# lapwing2p2.net
KiCad netlist of a schematic drawn in Altium Designer
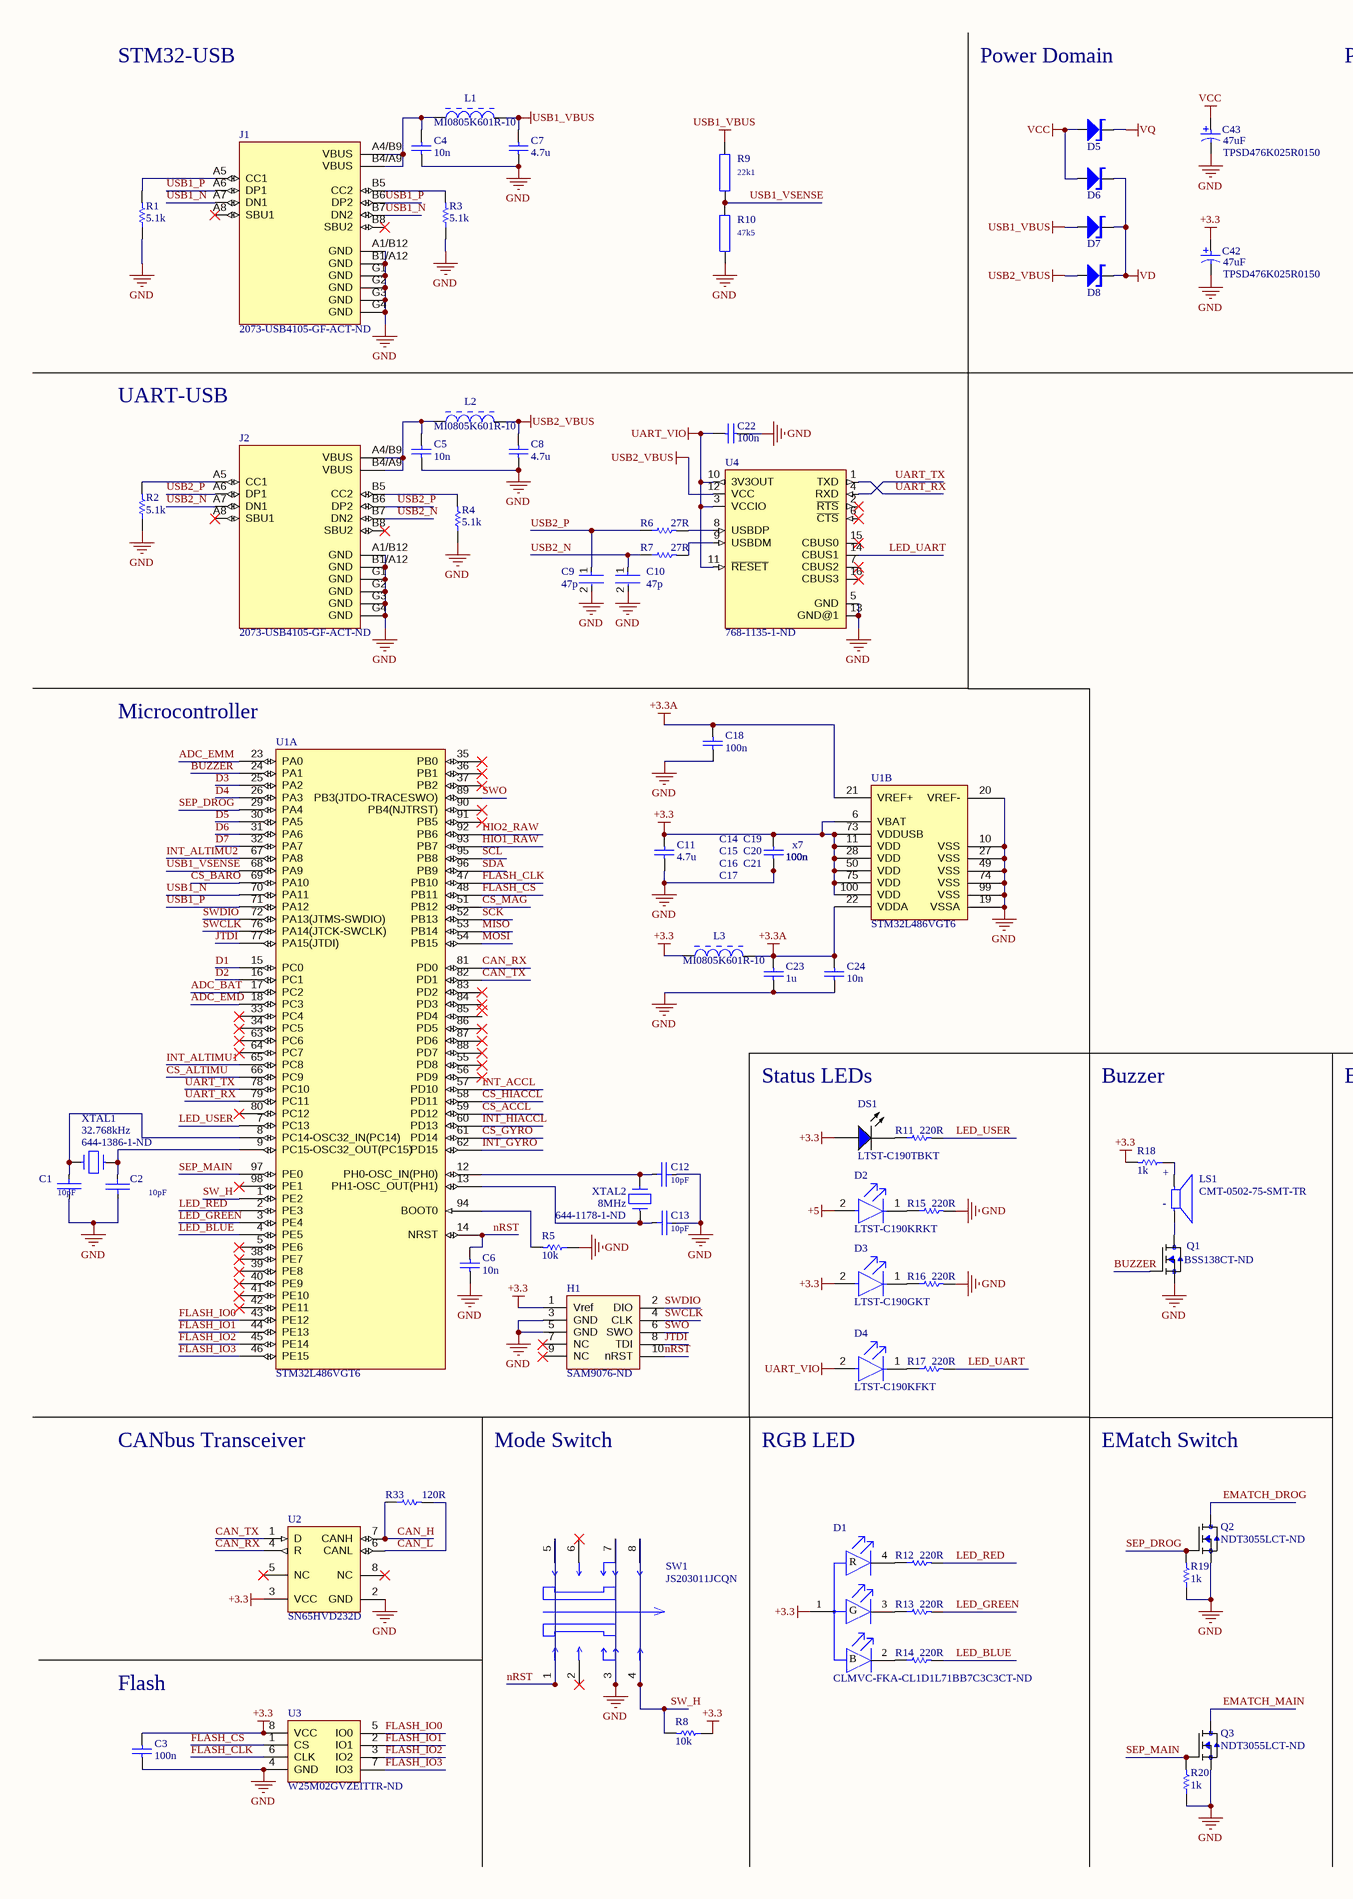
[diagram p0: lapwing2p2.SchDoc, left]
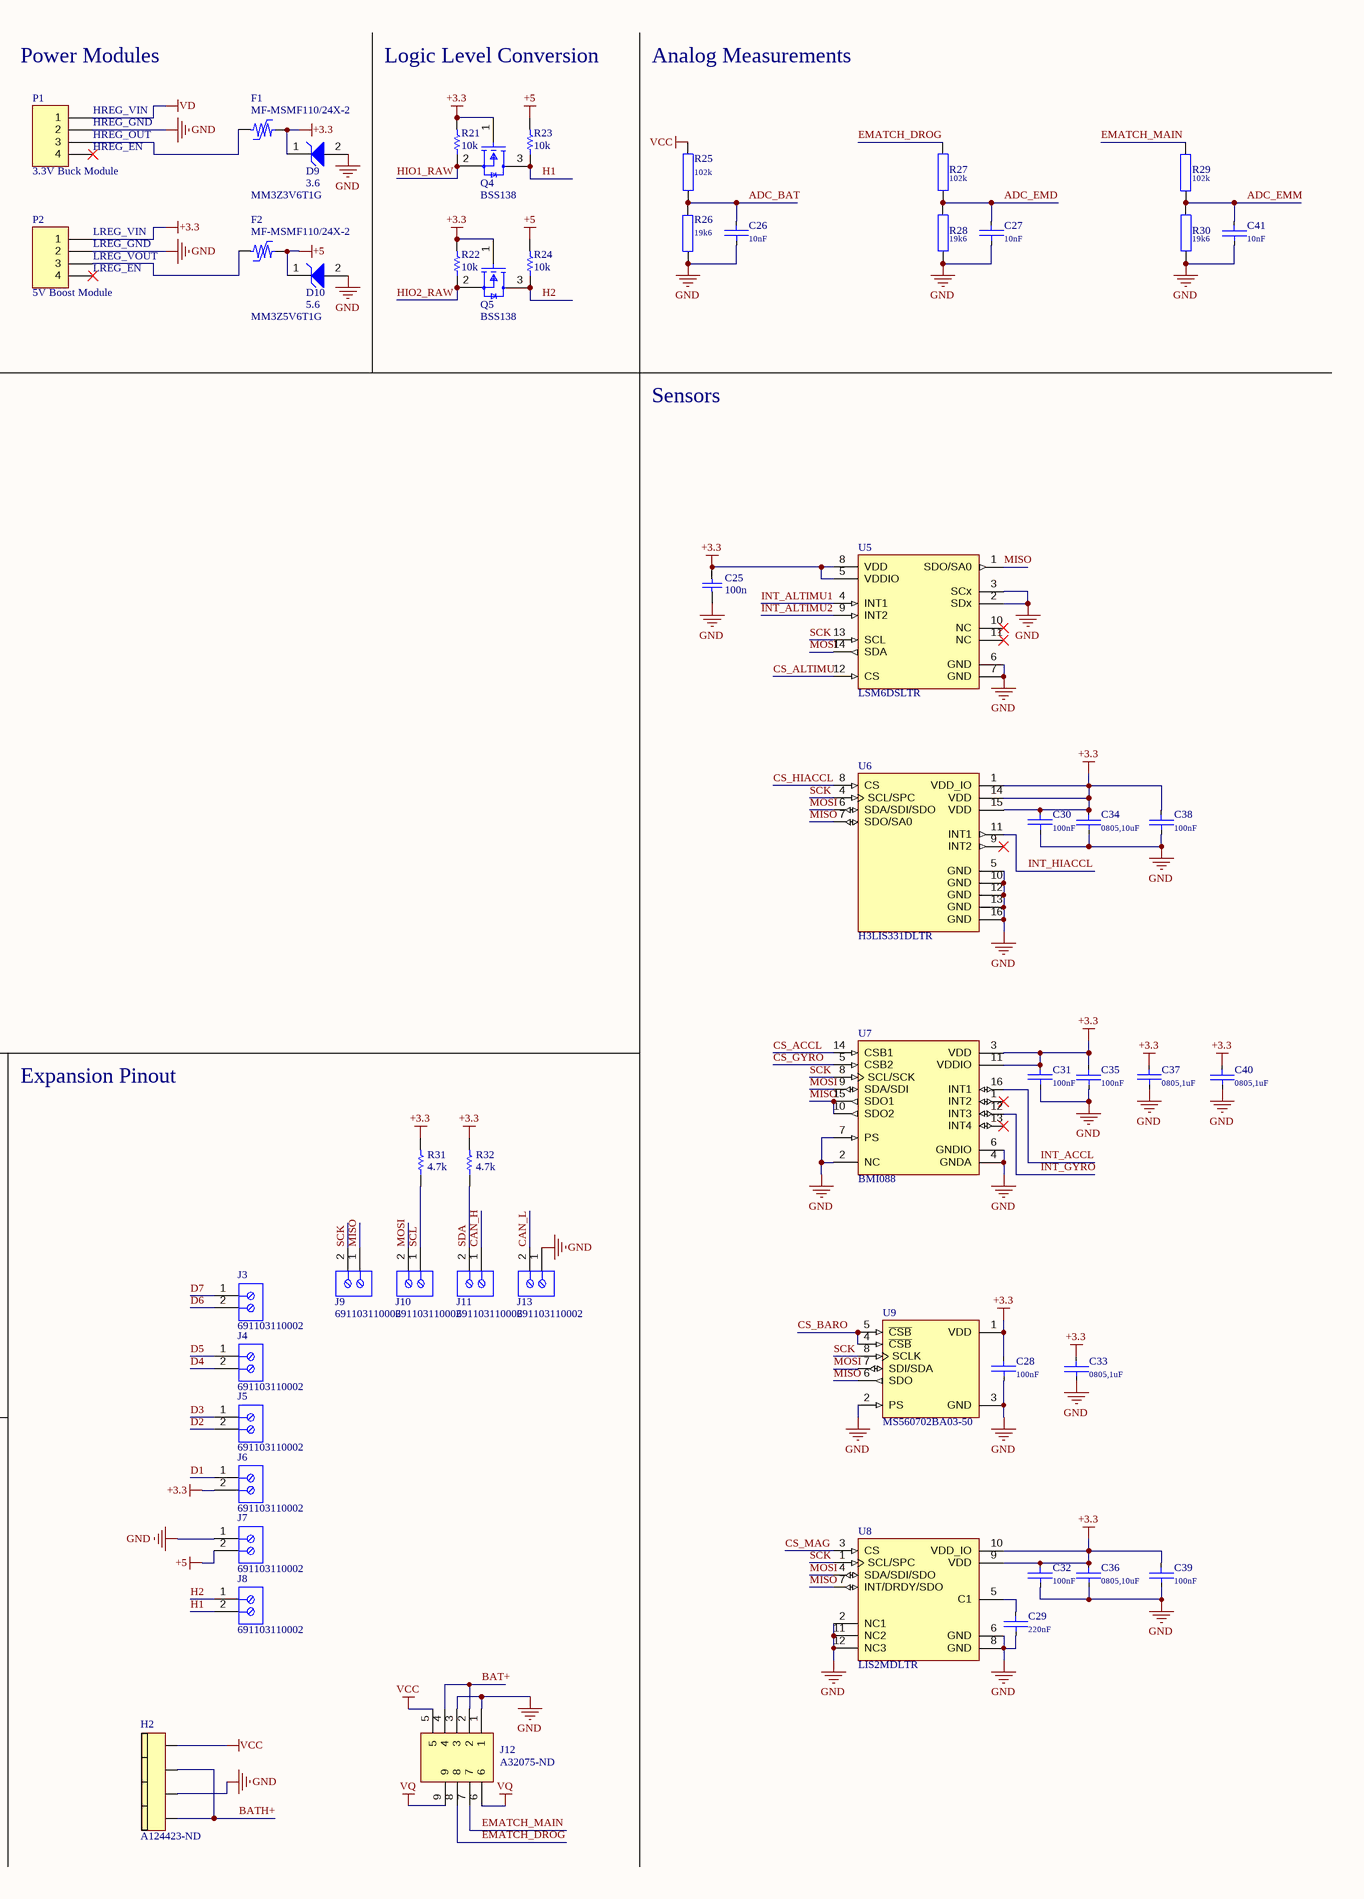
[diagram p1: lapwing2p2.SchDoc, right]

(export (version "E")
  (design (tool "Eeschema 10.0.6"))
  (components
    (comp (ref "C1")
      (value "CAP")
      (footprint "C0603")
      (description "CAPACITOR")
      (libsource (lib "Lapwing") (part "CAP"))
    )
    (comp (ref "C2")
      (value "CAP")
      (footprint "C0603")
      (description "CAPACITOR")
      (libsource (lib "Lapwing") (part "CAP"))
    )
    (comp (ref "C3")
      (value "100n")
      (footprint "CAPC1608X90X35ML10T15")
      (description "Chip Capacitor, 0.1 uF, +/- 10%, 50 V, -55 to 125 degC, 0603 (1608 Metric), RoHS, Tape and Reel")
      (fields (field (name "TOLERANCE") "10%") (field (name "VOLTAGE") "50V"))
      (libsource (lib "Altium Content Vault") (part "CAP-NP-2"))
    )
    (comp (ref "C4")
      (value "10n")
      (footprint "CAPC1608X90X35ML10T15")
      (description "Chip Capacitor, 10 nF, +/- 10%, 50 V, -55 to 125 degC, 0603 (1608 Metric), RoHS, Tape and Reel")
      (fields (field (name "VOLTAGE") "50V") (field (name "TOLERANCE") "10%"))
      (libsource (lib "Altium Content Vault") (part "CAP-NP-2"))
    )
    (comp (ref "C5")
      (value "10n")
      (footprint "CAPC1608X90X35ML10T15")
      (description "Chip Capacitor, 10 nF, +/- 10%, 50 V, -55 to 125 degC, 0603 (1608 Metric), RoHS, Tape and Reel")
      (fields (field (name "VOLTAGE") "50V") (field (name "TOLERANCE") "10%"))
      (libsource (lib "Altium Content Vault") (part "CAP-NP-2"))
    )
    (comp (ref "C6")
      (value "10n")
      (footprint "CAPC1608X90X35ML10T15")
      (description "Chip Capacitor, 10 nF, +/- 10%, 50 V, -55 to 125 degC, 0603 (1608 Metric), RoHS, Tape and Reel")
      (fields (field (name "VOLTAGE") "50V") (field (name "TOLERANCE") "10%"))
      (libsource (lib "Altium Content Vault") (part "CAP-NP-2"))
    )
    (comp (ref "C7")
      (value "4.7u")
      (footprint "CAPC2013X135X45NL10T25")
      (fields (field (name "PART NUMBER") "GRM21BR61E475KA12L") (field (name "MANUFACTURER") "Murata"))
      (libsource (lib "Altium Content Vault") (part "CAP"))
    )
    (comp (ref "C8")
      (value "4.7u")
      (footprint "CAPC2013X135X45NL10T25")
      (fields (field (name "PART NUMBER") "GRM21BR61E475KA12L") (field (name "MANUFACTURER") "Murata"))
      (libsource (lib "Altium Content Vault") (part "CAP"))
    )
    (comp (ref "C9")
      (value "47p")
      (footprint "FP-C0603C-CF-MFG")
      (description "CAP CER 47PF 50V C0G/NP0 0603")
      (fields (field (name "MANUFACTURER PART NUMBER") "C0603C470J5GACTU") (field (name "TOLERANCE") "0.05"))
      (libsource (lib "Altium Content Vault") (part "b4654b650e69147ec39a6b967a45e02"))
    )
    (comp (ref "C10")
      (value "47p")
      (footprint "FP-C0603C-CF-MFG")
      (description "CAP CER 47PF 50V C0G/NP0 0603")
      (fields (field (name "MANUFACTURER PART NUMBER") "C0603C470J5GACTU") (field (name "TOLERANCE") "0.05"))
      (libsource (lib "Altium Content Vault") (part "b4654b650e69147ec39a6b967a45e02"))
    )
    (comp (ref "C11")
      (value "4.7u")
      (footprint "CAPC2013X135X45NL10T25")
      (fields (field (name "PART NUMBER") "GRM21BR61E475KA12L") (field (name "MANUFACTURER") "Murata"))
      (libsource (lib "Altium Content Vault") (part "CAP"))
    )
    (comp (ref "C12")
      (value "CAP")
      (footprint "C0603")
      (description "CAPACITOR")
      (libsource (lib "Lapwing") (part "CAP"))
    )
    (comp (ref "C13")
      (value "CAP")
      (footprint "C0603")
      (description "CAPACITOR")
      (libsource (lib "Lapwing") (part "CAP"))
    )
    (comp (ref "C14")
      (value "100n")
      (footprint "CAPC1608X90X35ML10T15")
      (description "Chip Capacitor, 0.1 uF, +/- 10%, 50 V, -55 to 125 degC, 0603 (1608 Metric), RoHS, Tape and Reel")
      (fields (field (name "TOLERANCE") "10%") (field (name "VOLTAGE") "50V"))
      (libsource (lib "Altium Content Vault") (part "CAP-NP-2"))
    )
    (comp (ref "C15")
      (value "100n")
      (footprint "CAPC1608X90X35ML10T15")
      (description "Chip Capacitor, 0.1 uF, +/- 10%, 50 V, -55 to 125 degC, 0603 (1608 Metric), RoHS, Tape and Reel")
      (fields (field (name "TOLERANCE") "10%") (field (name "VOLTAGE") "50V"))
      (libsource (lib "Altium Content Vault") (part "CAP-NP-2"))
    )
    (comp (ref "C16")
      (value "100n")
      (footprint "CAPC1608X90X35ML10T15")
      (description "Chip Capacitor, 0.1 uF, +/- 10%, 50 V, -55 to 125 degC, 0603 (1608 Metric), RoHS, Tape and Reel")
      (fields (field (name "TOLERANCE") "10%") (field (name "VOLTAGE") "50V"))
      (libsource (lib "Altium Content Vault") (part "CAP-NP-2"))
    )
    (comp (ref "C17")
      (value "100n")
      (footprint "CAPC1608X90X35ML10T15")
      (description "Chip Capacitor, 0.1 uF, +/- 10%, 50 V, -55 to 125 degC, 0603 (1608 Metric), RoHS, Tape and Reel")
      (fields (field (name "TOLERANCE") "10%") (field (name "VOLTAGE") "50V"))
      (libsource (lib "Altium Content Vault") (part "CAP-NP-2"))
    )
    (comp (ref "C18")
      (value "100n")
      (footprint "CAPC1608X90X35ML10T15")
      (description "Chip Capacitor, 0.1 uF, +/- 10%, 50 V, -55 to 125 degC, 0603 (1608 Metric), RoHS, Tape and Reel")
      (fields (field (name "TOLERANCE") "10%") (field (name "VOLTAGE") "50V"))
      (libsource (lib "Altium Content Vault") (part "CAP-NP-2"))
    )
    (comp (ref "C19")
      (value "100n")
      (footprint "CAPC1608X90X35ML10T15")
      (description "Chip Capacitor, 0.1 uF, +/- 10%, 50 V, -55 to 125 degC, 0603 (1608 Metric), RoHS, Tape and Reel")
      (fields (field (name "TOLERANCE") "10%") (field (name "VOLTAGE") "50V"))
      (libsource (lib "Altium Content Vault") (part "CAP-NP-2"))
    )
    (comp (ref "C20")
      (value "100n")
      (footprint "CAPC1608X90X35ML10T15")
      (description "Chip Capacitor, 0.1 uF, +/- 10%, 50 V, -55 to 125 degC, 0603 (1608 Metric), RoHS, Tape and Reel")
      (fields (field (name "TOLERANCE") "10%") (field (name "VOLTAGE") "50V"))
      (libsource (lib "Altium Content Vault") (part "CAP-NP-2"))
    )
    (comp (ref "C21")
      (value "100n")
      (footprint "CAPC1608X90X35ML10T15")
      (description "Chip Capacitor, 0.1 uF, +/- 10%, 50 V, -55 to 125 degC, 0603 (1608 Metric), RoHS, Tape and Reel")
      (fields (field (name "TOLERANCE") "10%") (field (name "VOLTAGE") "50V"))
      (libsource (lib "Altium Content Vault") (part "CAP-NP-2"))
    )
    (comp (ref "C22")
      (value "100n")
      (footprint "CAPC1608X90X35ML10T15")
      (description "Chip Capacitor, 0.1 uF, +/- 10%, 50 V, -55 to 125 degC, 0603 (1608 Metric), RoHS, Tape and Reel")
      (fields (field (name "TOLERANCE") "10%") (field (name "VOLTAGE") "50V"))
      (libsource (lib "Altium Content Vault") (part "CAP-NP-2"))
    )
    (comp (ref "C23")
      (value "1u")
      (footprint "CAPC1608X90X35NL10T15")
      (fields (field (name "MANUFACTURER") "Murata") (field (name "PART NUMBER") "GRM188R71E105KA12D"))
      (libsource (lib "Altium Content Vault") (part "CAP"))
    )
    (comp (ref "C24")
      (value "10n")
      (footprint "CAPC1608X90X35ML10T15")
      (description "Chip Capacitor, 10 nF, +/- 10%, 50 V, -55 to 125 degC, 0603 (1608 Metric), RoHS, Tape and Reel")
      (fields (field (name "VOLTAGE") "50V") (field (name "TOLERANCE") "10%"))
      (libsource (lib "Altium Content Vault") (part "CAP-NP-2"))
    )
    (comp (ref "C25")
      (value "100n")
      (footprint "CAPC1608X90X35ML10T15")
      (description "Chip Capacitor, 0.1 uF, +/- 10%, 50 V, -55 to 125 degC, 0603 (1608 Metric), RoHS, Tape and Reel")
      (fields (field (name "TOLERANCE") "10%") (field (name "VOLTAGE") "50V"))
      (libsource (lib "Altium Content Vault") (part "CAP-NP-2"))
    )
    (comp (ref "C26")
      (value "CAP")
      (footprint "C0603")
      (description "CAPACITOR")
      (libsource (lib "Lapwing") (part "CAP"))
    )
    (comp (ref "C27")
      (value "CAP")
      (footprint "C0603")
      (description "CAPACITOR")
      (libsource (lib "Lapwing") (part "CAP"))
    )
    (comp (ref "C28")
      (value "CAP")
      (footprint "C0603")
      (description "CAPACITOR")
      (libsource (lib "Lapwing") (part "CAP"))
    )
    (comp (ref "C29")
      (value "CAP")
      (footprint "C0603")
      (description "CAPACITOR")
      (libsource (lib "Lapwing") (part "CAP"))
    )
    (comp (ref "C30")
      (value "CAP")
      (footprint "C0603")
      (description "CAPACITOR")
      (libsource (lib "Lapwing") (part "CAP"))
    )
    (comp (ref "C31")
      (value "CAP")
      (footprint "C0603")
      (description "CAPACITOR")
      (libsource (lib "Lapwing") (part "CAP"))
    )
    (comp (ref "C32")
      (value "CAP")
      (footprint "C0603")
      (description "CAPACITOR")
      (libsource (lib "Lapwing") (part "CAP"))
    )
    (comp (ref "C33")
      (value "CAP")
      (footprint "C0805")
      (description "CAPACITOR")
      (libsource (lib "Lapwing") (part "CAP"))
    )
    (comp (ref "C34")
      (value "CAP")
      (footprint "C0805")
      (description "CAPACITOR")
      (libsource (lib "Lapwing") (part "CAP"))
    )
    (comp (ref "C35")
      (value "CAP")
      (footprint "C0603")
      (description "CAPACITOR")
      (libsource (lib "Lapwing") (part "CAP"))
    )
    (comp (ref "C36")
      (value "CAP")
      (footprint "C0805")
      (description "CAPACITOR")
      (libsource (lib "Lapwing") (part "CAP"))
    )
    (comp (ref "C37")
      (value "CAP")
      (footprint "C0805")
      (description "CAPACITOR")
      (libsource (lib "Lapwing") (part "CAP"))
    )
    (comp (ref "C38")
      (value "CAP")
      (footprint "C0603")
      (description "CAPACITOR")
      (libsource (lib "Lapwing") (part "CAP"))
    )
    (comp (ref "C39")
      (value "CAP")
      (footprint "C0603")
      (description "CAPACITOR")
      (libsource (lib "Lapwing") (part "CAP"))
    )
    (comp (ref "C40")
      (value "CAP")
      (footprint "C0805")
      (description "CAPACITOR")
      (libsource (lib "Lapwing") (part "CAP"))
    )
    (comp (ref "C41")
      (value "CAP")
      (footprint "C0603")
      (description "CAPACITOR")
      (libsource (lib "Lapwing") (part "CAP"))
    )
    (comp (ref "C42")
      (value "TPSD476K025R0150")
      (footprint "AVX-7343-31_L")
      (description "Tantalum Capacitor, 47 uF, +/- 10%, 25 V, -55 to 125 degC, 2-Pin SMD, Tape and Reel")
      (fields
        (field (name "TOLERANCE") "10%")
        (field (name "MANUFACTURER") "AVX")
        (field (name "ALTIUM_VALUE") "47uF")
      )
      (libsource (lib "Altium Content Vault") (part "CAP-P-2"))
    )
    (comp (ref "C43")
      (value "TPSD476K025R0150")
      (footprint "AVX-7343-31_L")
      (description "Tantalum Capacitor, 47 uF, +/- 10%, 25 V, -55 to 125 degC, 2-Pin SMD, Tape and Reel")
      (fields
        (field (name "TOLERANCE") "10%")
        (field (name "MANUFACTURER") "AVX")
        (field (name "ALTIUM_VALUE") "47uF")
      )
      (libsource (lib "Altium Content Vault") (part "CAP-P-2"))
    )
    (comp (ref "D1")
      (value "CLMVC-FKA-CL1D1L71BB7C3C3")
      (footprint "CLMVC-FKA")
      (description "LED RGB CLEAR 4PLCC SMD")
      (fields
        (field (name "DIGI-KEY_PART_NUMBER") "CLMVC-FKA-CL1D1L71BB7C3C3CT-ND")
        (field (name "MF") "Cree Inc.")
        (field (name "SUPPLIER PART NUMBER 1") "CLMVC-FKA-CL1D1L71BB7C3C3CT-ND")
      )
      (libsource (lib "Lapwing") (part "CLMVC-FKA-CL1D1L71BB7C3C3"))
    )
    (comp (ref "D2")
      (value "LTST-C190KRKT")
      (footprint "FP-LTST-C190KRKT-MFG")
      (description "LED RED CLEAR CHIP SMD")
      (libsource (lib "Altium Content Vault") (part "8706943c75ba83719d021d2fdc84c58"))
    )
    (comp (ref "D3")
      (value "LTST-C190GKT")
      (footprint "FP-LTST-C190GKT-MFG")
      (description "LED GREEN CLEAR CHIP SMD")
      (fields (field (name "VOLTAGE") "2V"))
      (libsource (lib "Altium Content Vault") (part "8706943c75ba83719d021d2fdc84c58"))
    )
    (comp (ref "D4")
      (value "LTST-C190KFKT")
      (footprint "FP-LTST-C190KFKT-MFG")
      (description "LED ORANGE CLEAR CHIP SMD")
      (libsource (lib "Altium Content Vault") (part "8706943c75ba83719d021d2fdc84c58"))
    )
    (comp (ref "D5")
      (value "PMEG6030EVPX")
      (footprint "D_PMEG6030EVPX")
      (description "DIODE SCHOTTKY 60V 3A SOD128")
      (libsource (lib "Lapwing") (part "PMEG6030EVPX"))
    )
    (comp (ref "D6")
      (value "PMEG6030EVPX")
      (footprint "D_PMEG6030EVPX")
      (description "DIODE SCHOTTKY 60V 3A SOD128")
      (libsource (lib "Lapwing") (part "PMEG6030EVPX"))
    )
    (comp (ref "D7")
      (value "PMEG6030EVPX")
      (footprint "D_PMEG6030EVPX")
      (description "DIODE SCHOTTKY 60V 3A SOD128")
      (libsource (lib "Lapwing") (part "PMEG6030EVPX"))
    )
    (comp (ref "D8")
      (value "PMEG6030EVPX")
      (footprint "D_PMEG6030EVPX")
      (description "DIODE SCHOTTKY 60V 3A SOD128")
      (libsource (lib "Lapwing") (part "PMEG6030EVPX"))
    )
    (comp (ref "D9")
      (value "MM3Z3V6T1G")
      (footprint "ONSC-SOD-323-2-477-02_V")
      (description "Zener Voltage Regulator, 300 mW, 2-Pin SOD-323, Pb-Free, Tape and Reel")
      (fields (field (name "VZ TYP (V)") "3.6") (field (name "MANUFACTURER") "On Semiconductor"))
      (libsource (lib "Altium Content Vault") (part "ONSC-K1A2-2"))
    )
    (comp (ref "D10")
      (value "MM3Z5V6T1G")
      (footprint "ONSC-SOD-323-2-477-02_V")
      (description "Zener Voltage Regulator, 300 mW, 2-Pin SOD-323, Pb-Free, Tape and Reel")
      (fields (field (name "MANUFACTURER") "On Semiconductor") (field (name "VZ TYP (V)") "5.6"))
      (libsource (lib "Altium Content Vault") (part "ONSC-K1A2-2"))
    )
    (comp (ref "DS1")
      (value "LTST-C190TBKT")
      (footprint "LTST-C190TBKT-2_V")
      (description "Single Color Chip LED, 2.8 to 3.8 V, 28 to 180 mcd, -20 to 80 degC, 2-Pin SMD, RoHS, Tape and Reel")
      (libsource (lib "Altium Content Vault") (part "LED-BLUE-AK-2"))
    )
    (comp (ref "F1")
      (value "MF-MSMF110/24X-2")
      (footprint "BOUR-MF-MSMF110-24X-2_V")
      (description "PTC Resettable Fuse, 24 V, 1.1 A, -40 to 85 degC, 2-Pin SMD, RoHS, Tape and Reel")
      (fields (field (name "MANUFACTURER") "Bourns"))
      (libsource (lib "Altium Content Vault") (part "PPTC-2"))
    )
    (comp (ref "F2")
      (value "MF-MSMF110/24X-2")
      (footprint "BOUR-MF-MSMF110-24X-2_V")
      (description "PTC Resettable Fuse, 24 V, 1.1 A, -40 to 85 degC, 2-Pin SMD, RoHS, Tape and Reel")
      (fields (field (name "MANUFACTURER") "Bourns"))
      (libsource (lib "Altium Content Vault") (part "PPTC-2"))
    )
    (comp (ref "H1")
      (value "FTSH-105-01-L-DV-K-P")
      (footprint "H_FTSH-105-01-L-DV-K-P")
      (description "CONN HEADER SMD 10POS 1.27MM")
      (fields (field (name "SUPPLIER PART NUMBER 1") "SAM9076-ND"))
      (libsource (lib "Lapwing") (part "FTSH-105-01-L-DV-K-P"))
    )
    (comp (ref "H2")
      (value "282837-4")
      (footprint "H_282837-4")
      (description "TERM BLK 4P SIDE ENT 5.08MM PCB")
      (fields (field (name "SUPPLIER PART NUMBER 1") "A124423-ND"))
      (libsource (lib "Lapwing") (part "282837-4"))
    )
    (comp (ref "J1")
      (value "USB4105-GF-A")
      (footprint "H_GCT_USB4105-GF-A")
      (description "CONN RCPT USB2.0 TYPEC 5A")
      (fields (field (name "MF") "GCT") (field (name "SUPPLIER PART NUMBER 1") "2073-USB4105-GF-ACT-ND"))
      (libsource (lib "Lapwing") (part "USB4105-GF-A"))
    )
    (comp (ref "J2")
      (value "USB4105-GF-A")
      (footprint "H_GCT_USB4105-GF-A")
      (description "CONN RCPT USB2.0 TYPEC 5A")
      (fields (field (name "MF") "GCT") (field (name "SUPPLIER PART NUMBER 1") "2073-USB4105-GF-ACT-ND"))
      (libsource (lib "Lapwing") (part "USB4105-GF-A"))
    )
    (comp (ref "J3")
      (value "691103110002")
      (footprint "691103110002")
      (description "Series 1031 - 3.50 mm Horizontal Entry Modular with Pressure Clamp WR-TBL, 2 pin")
      (fields (field (name "MANUFACTURER") "Wurth Elektronik") (field (name "PUBLISHER") "WurthElektronik"))
      (libsource (lib "Altium Content Vault") (part "WE-CN-1P-F-TB2"))
    )
    (comp (ref "J4")
      (value "691103110002")
      (footprint "691103110002")
      (description "Series 1031 - 3.50 mm Horizontal Entry Modular with Pressure Clamp WR-TBL, 2 pin")
      (fields (field (name "MANUFACTURER") "Wurth Elektronik") (field (name "PUBLISHER") "WurthElektronik"))
      (libsource (lib "Altium Content Vault") (part "WE-CN-1P-F-TB2"))
    )
    (comp (ref "J5")
      (value "691103110002")
      (footprint "691103110002")
      (description "Series 1031 - 3.50 mm Horizontal Entry Modular with Pressure Clamp WR-TBL, 2 pin")
      (fields (field (name "MANUFACTURER") "Wurth Elektronik") (field (name "PUBLISHER") "WurthElektronik"))
      (libsource (lib "Altium Content Vault") (part "WE-CN-1P-F-TB2"))
    )
    (comp (ref "J6")
      (value "691103110002")
      (footprint "691103110002")
      (description "Series 1031 - 3.50 mm Horizontal Entry Modular with Pressure Clamp WR-TBL, 2 pin")
      (fields (field (name "MANUFACTURER") "Wurth Elektronik") (field (name "PUBLISHER") "WurthElektronik"))
      (libsource (lib "Altium Content Vault") (part "WE-CN-1P-F-TB2"))
    )
    (comp (ref "J7")
      (value "691103110002")
      (footprint "691103110002")
      (description "Series 1031 - 3.50 mm Horizontal Entry Modular with Pressure Clamp WR-TBL, 2 pin")
      (fields (field (name "MANUFACTURER") "Wurth Elektronik") (field (name "PUBLISHER") "WurthElektronik"))
      (libsource (lib "Altium Content Vault") (part "WE-CN-1P-F-TB2"))
    )
    (comp (ref "J8")
      (value "691103110002")
      (footprint "691103110002")
      (description "Series 1031 - 3.50 mm Horizontal Entry Modular with Pressure Clamp WR-TBL, 2 pin")
      (fields (field (name "MANUFACTURER") "Wurth Elektronik") (field (name "PUBLISHER") "WurthElektronik"))
      (libsource (lib "Altium Content Vault") (part "WE-CN-1P-F-TB2"))
    )
    (comp (ref "J9")
      (value "691103110002")
      (footprint "691103110002")
      (description "Series 1031 - 3.50 mm Horizontal Entry Modular with Pressure Clamp WR-TBL, 2 pin")
      (fields (field (name "MANUFACTURER") "Wurth Elektronik") (field (name "PUBLISHER") "WurthElektronik"))
      (libsource (lib "Altium Content Vault") (part "WE-CN-1P-F-TB2"))
    )
    (comp (ref "J10")
      (value "691103110002")
      (footprint "691103110002")
      (description "Series 1031 - 3.50 mm Horizontal Entry Modular with Pressure Clamp WR-TBL, 2 pin")
      (fields (field (name "MANUFACTURER") "Wurth Elektronik") (field (name "PUBLISHER") "WurthElektronik"))
      (libsource (lib "Altium Content Vault") (part "WE-CN-1P-F-TB2"))
    )
    (comp (ref "J11")
      (value "691103110002")
      (footprint "691103110002")
      (description "Series 1031 - 3.50 mm Horizontal Entry Modular with Pressure Clamp WR-TBL, 2 pin")
      (fields (field (name "MANUFACTURER") "Wurth Elektronik") (field (name "PUBLISHER") "WurthElektronik"))
      (libsource (lib "Altium Content Vault") (part "WE-CN-1P-F-TB2"))
    )
    (comp (ref "J12")
      (value "5745781-4")
      (footprint "J_5745781-4")
      (description "CONN D-SUB RCPT 9POS R/A SOLDER")
      (fields
        (field (name "DIGI-KEY_PART_NUMBER") "A32075-ND")
        (field (name "MF") "TE Connectivity")
        (field (name "SUPPLIER PART NUMBER 1") "A32075-ND")
      )
      (libsource (lib "Lapwing") (part "5745781-4"))
    )
    (comp (ref "J13")
      (value "691103110002")
      (footprint "691103110002")
      (description "Series 1031 - 3.50 mm Horizontal Entry Modular with Pressure Clamp WR-TBL, 2 pin")
      (fields (field (name "MANUFACTURER") "Wurth Elektronik") (field (name "PUBLISHER") "WurthElektronik"))
      (libsource (lib "Altium Content Vault") (part "WE-CN-1P-F-TB2"))
    )
    (comp (ref "L1")
      (value "MI0805K601R-10")
      (footprint "LIRD-MI0805K601R-10-2_V")
      (fields (field (name "MANUFACTURER") "Laird"))
      (libsource (lib "Altium Content Vault") (part "IND-FB-2"))
    )
    (comp (ref "L2")
      (value "MI0805K601R-10")
      (footprint "LIRD-MI0805K601R-10-2_V")
      (fields (field (name "MANUFACTURER") "Laird"))
      (libsource (lib "Altium Content Vault") (part "IND-FB-2"))
    )
    (comp (ref "L3")
      (value "MI0805K601R-10")
      (footprint "LIRD-MI0805K601R-10-2_V")
      (fields (field (name "MANUFACTURER") "Laird"))
      (libsource (lib "Altium Content Vault") (part "IND-FB-2"))
    )
    (comp (ref "LS1")
      (value "CMT-0502-75-SMT-TR")
      (footprint "XDCR_CMT-0502-75-SMT-TR")
      (description "BUZZER, 5 MM, 2 MM DEEP, M, 3 V,")
      (fields (field (name "MF") "CUI Devices"))
      (libsource (lib "Lapwing") (part "CMT-0502-75-SMT-TR"))
    )
    (comp (ref "P1")
      (value "3.3V Buck Module")
      (footprint "HDR1X4")
      (description "Header, 4-Pin")
      (fields (field (name "PUBLISHER") "Altium Limited"))
      (libsource (lib "Miscellaneous Connectors") (part "Header 4"))
    )
    (comp (ref "P2")
      (value "5V Boost Module")
      (footprint "HDR1X4")
      (description "Header, 4-Pin")
      (fields (field (name "PUBLISHER") "Altium Limited"))
      (libsource (lib "Miscellaneous Connectors") (part "Header 4"))
    )
    (comp (ref "Q1")
      (value "BSS138")
      (footprint "Q_BSS138")
      (description "MOSFET N-CH 50V 220MA SOT-23")
      (fields (field (name "SUPPLIER PART NUMBER 1") "BSS138CT-ND"))
      (libsource (lib "Lapwing") (part "BSS138"))
    )
    (comp (ref "Q2")
      (value "NDT3055L")
      (footprint "Q_NDT3055L")
      (description "MOSFET N-CH 60V 4A SOT-223-4")
      (fields (field (name "SUPPLIER PART NUMBER 1") "NDT3055LCT-ND"))
      (libsource (lib "Lapwing") (part "NDT3055L"))
    )
    (comp (ref "Q3")
      (value "NDT3055L")
      (footprint "Q_NDT3055L")
      (description "MOSFET N-CH 60V 4A SOT-223-4")
      (fields (field (name "SUPPLIER PART NUMBER 1") "NDT3055LCT-ND"))
      (libsource (lib "Lapwing") (part "NDT3055L"))
    )
    (comp (ref "Q4")
      (value "BSS138")
      (footprint "FP-318-08-IPC_B")
      (description "MOSFET N-CH 50V 220MA SOT-23")
      (libsource (lib "Altium Content Vault") (part "3b9c635fedb024a5347a57b145af9cc"))
    )
    (comp (ref "Q5")
      (value "BSS138")
      (footprint "FP-318-08-IPC_B")
      (description "MOSFET N-CH 50V 220MA SOT-23")
      (libsource (lib "Altium Content Vault") (part "3b9c635fedb024a5347a57b145af9cc"))
    )
    (comp (ref "R1")
      (value "5.1k")
      (footprint "RESC1608X55X30NL15T15")
      (fields (field (name "PART NUMBER") "ERJ-3EKF5101V") (field (name "MANUFACTURER") "Panasonic"))
      (libsource (lib "Altium Content Vault") (part "RES"))
    )
    (comp (ref "R2")
      (value "5.1k")
      (footprint "RESC1608X55X30NL15T15")
      (fields (field (name "PART NUMBER") "ERJ-3EKF5101V") (field (name "MANUFACTURER") "Panasonic"))
      (libsource (lib "Altium Content Vault") (part "RES"))
    )
    (comp (ref "R3")
      (value "5.1k")
      (footprint "RESC1608X55X30NL15T15")
      (fields (field (name "PART NUMBER") "ERJ-3EKF5101V") (field (name "MANUFACTURER") "Panasonic"))
      (libsource (lib "Altium Content Vault") (part "RES"))
    )
    (comp (ref "R4")
      (value "5.1k")
      (footprint "RESC1608X55X30NL15T15")
      (fields (field (name "PART NUMBER") "ERJ-3EKF5101V") (field (name "MANUFACTURER") "Panasonic"))
      (libsource (lib "Altium Content Vault") (part "RES"))
    )
    (comp (ref "R5")
      (value "10k")
      (footprint "RESC1609X55X30LL15T15")
      (description "Chip Resistor, 10 KOhm, +/- 1%, 0.1 W, -55 to 155 degC, 0603 (1608 Metric), RoHS, Tape and Reel")
      (fields (field (name "TOLERANCE") "1%") (field (name "MANUFACTURER") "Panasonic"))
      (libsource (lib "Altium Content Vault") (part "RES-2"))
    )
    (comp (ref "R6")
      (value "27R")
      (footprint "RESC1608X55X30NL15T15")
      (fields (field (name "MANUFACTURER") "Panasonic") (field (name "PART NUMBER") "ERJ3EKF27R0V"))
      (libsource (lib "Altium Content Vault") (part "RES"))
    )
    (comp (ref "R7")
      (value "27R")
      (footprint "RESC1608X55X30NL15T15")
      (fields (field (name "MANUFACTURER") "Panasonic") (field (name "PART NUMBER") "ERJ3EKF27R0V"))
      (libsource (lib "Altium Content Vault") (part "RES"))
    )
    (comp (ref "R8")
      (value "10k")
      (footprint "RESC1609X55X30LL15T15")
      (description "Chip Resistor, 10 KOhm, +/- 1%, 0.1 W, -55 to 155 degC, 0603 (1608 Metric), RoHS, Tape and Reel")
      (fields (field (name "TOLERANCE") "1%") (field (name "MANUFACTURER") "Panasonic"))
      (libsource (lib "Altium Content Vault") (part "RES-2"))
    )
    (comp (ref "R9")
      (value "RES")
      (footprint "R0603")
      (description "RESISTOR")
      (libsource (lib "Lapwing") (part "RES"))
    )
    (comp (ref "R10")
      (value "RES")
      (footprint "R0603")
      (description "RESISTOR")
      (libsource (lib "Lapwing") (part "RES"))
    )
    (comp (ref "R11")
      (value "220R")
      (footprint "RESC1608X55X30LL15T15")
      (description "Chip Resistor, 220 Ohm, +/- 1%, 0.1 W, -55 to 155 degC, 0603 (1608 Metric), RoHS, Tape and Reel")
      (fields (field (name "TOLERANCE") "1%") (field (name "Comment") "ERJ-3EKF2200V"))
      (libsource (lib "Altium Content Vault") (part "RES-2"))
    )
    (comp (ref "R12")
      (value "220R")
      (footprint "RESC1608X55X30LL15T15")
      (description "Chip Resistor, 220 Ohm, +/- 1%, 0.1 W, -55 to 155 degC, 0603 (1608 Metric), RoHS, Tape and Reel")
      (fields (field (name "TOLERANCE") "1%") (field (name "Comment") "ERJ-3EKF2200V"))
      (libsource (lib "Altium Content Vault") (part "RES-2"))
    )
    (comp (ref "R13")
      (value "220R")
      (footprint "RESC1608X55X30LL15T15")
      (description "Chip Resistor, 220 Ohm, +/- 1%, 0.1 W, -55 to 155 degC, 0603 (1608 Metric), RoHS, Tape and Reel")
      (fields (field (name "TOLERANCE") "1%") (field (name "Comment") "ERJ-3EKF2200V"))
      (libsource (lib "Altium Content Vault") (part "RES-2"))
    )
    (comp (ref "R14")
      (value "220R")
      (footprint "RESC1608X55X30LL15T15")
      (description "Chip Resistor, 220 Ohm, +/- 1%, 0.1 W, -55 to 155 degC, 0603 (1608 Metric), RoHS, Tape and Reel")
      (fields (field (name "TOLERANCE") "1%") (field (name "Comment") "ERJ-3EKF2200V"))
      (libsource (lib "Altium Content Vault") (part "RES-2"))
    )
    (comp (ref "R15")
      (value "220R")
      (footprint "RESC1608X55X30LL15T15")
      (description "Chip Resistor, 220 Ohm, +/- 1%, 0.1 W, -55 to 155 degC, 0603 (1608 Metric), RoHS, Tape and Reel")
      (fields (field (name "TOLERANCE") "1%") (field (name "Comment") "ERJ-3EKF2200V"))
      (libsource (lib "Altium Content Vault") (part "RES-2"))
    )
    (comp (ref "R16")
      (value "220R")
      (footprint "RESC1608X55X30LL15T15")
      (description "Chip Resistor, 220 Ohm, +/- 1%, 0.1 W, -55 to 155 degC, 0603 (1608 Metric), RoHS, Tape and Reel")
      (fields (field (name "TOLERANCE") "1%") (field (name "Comment") "ERJ-3EKF2200V"))
      (libsource (lib "Altium Content Vault") (part "RES-2"))
    )
    (comp (ref "R17")
      (value "220R")
      (footprint "RESC1608X55X30LL15T15")
      (description "Chip Resistor, 220 Ohm, +/- 1%, 0.1 W, -55 to 155 degC, 0603 (1608 Metric), RoHS, Tape and Reel")
      (fields (field (name "TOLERANCE") "1%") (field (name "Comment") "ERJ-3EKF2200V"))
      (libsource (lib "Altium Content Vault") (part "RES-2"))
    )
    (comp (ref "R18")
      (value "1k")
      (footprint "RESC1608X55X30ML15T15")
      (fields (field (name "PART NUMBER") "ERJ-3EKF1001V") (field (name "MANUFACTURER") "Panasonic"))
      (libsource (lib "Altium Content Vault") (part "RES"))
    )
    (comp (ref "R19")
      (value "1k")
      (footprint "RESC1608X55X30ML15T15")
      (fields (field (name "PART NUMBER") "ERJ-3EKF1001V") (field (name "MANUFACTURER") "Panasonic"))
      (libsource (lib "Altium Content Vault") (part "RES"))
    )
    (comp (ref "R20")
      (value "1k")
      (footprint "RESC1608X55X30ML15T15")
      (fields (field (name "PART NUMBER") "ERJ-3EKF1001V") (field (name "MANUFACTURER") "Panasonic"))
      (libsource (lib "Altium Content Vault") (part "RES"))
    )
    (comp (ref "R21")
      (value "10k")
      (footprint "RESC1609X55X30LL15T15")
      (description "Chip Resistor, 10 KOhm, +/- 1%, 0.1 W, -55 to 155 degC, 0603 (1608 Metric), RoHS, Tape and Reel")
      (fields (field (name "TOLERANCE") "1%") (field (name "MANUFACTURER") "Panasonic"))
      (libsource (lib "Altium Content Vault") (part "RES-2"))
    )
    (comp (ref "R22")
      (value "10k")
      (footprint "RESC1609X55X30LL15T15")
      (description "Chip Resistor, 10 KOhm, +/- 1%, 0.1 W, -55 to 155 degC, 0603 (1608 Metric), RoHS, Tape and Reel")
      (fields (field (name "TOLERANCE") "1%") (field (name "MANUFACTURER") "Panasonic"))
      (libsource (lib "Altium Content Vault") (part "RES-2"))
    )
    (comp (ref "R23")
      (value "10k")
      (footprint "RESC1609X55X30LL15T15")
      (description "Chip Resistor, 10 KOhm, +/- 1%, 0.1 W, -55 to 155 degC, 0603 (1608 Metric), RoHS, Tape and Reel")
      (fields (field (name "TOLERANCE") "1%") (field (name "MANUFACTURER") "Panasonic"))
      (libsource (lib "Altium Content Vault") (part "RES-2"))
    )
    (comp (ref "R24")
      (value "10k")
      (footprint "RESC1609X55X30LL15T15")
      (description "Chip Resistor, 10 KOhm, +/- 1%, 0.1 W, -55 to 155 degC, 0603 (1608 Metric), RoHS, Tape and Reel")
      (fields (field (name "TOLERANCE") "1%") (field (name "MANUFACTURER") "Panasonic"))
      (libsource (lib "Altium Content Vault") (part "RES-2"))
    )
    (comp (ref "R25")
      (value "RES")
      (footprint "R0603")
      (description "RESISTOR")
      (libsource (lib "Lapwing") (part "RES"))
    )
    (comp (ref "R26")
      (value "RES")
      (footprint "R0603")
      (description "RESISTOR")
      (libsource (lib "Lapwing") (part "RES"))
    )
    (comp (ref "R27")
      (value "RES")
      (footprint "R0603")
      (description "RESISTOR")
      (libsource (lib "Lapwing") (part "RES"))
    )
    (comp (ref "R28")
      (value "RES")
      (footprint "R0603")
      (description "RESISTOR")
      (libsource (lib "Lapwing") (part "RES"))
    )
    (comp (ref "R29")
      (value "RES")
      (footprint "R0603")
      (description "RESISTOR")
      (libsource (lib "Lapwing") (part "RES"))
    )
    (comp (ref "R30")
      (value "RES")
      (footprint "R0603")
      (description "RESISTOR")
      (libsource (lib "Lapwing") (part "RES"))
    )
    (comp (ref "R31")
      (value "4.7k")
      (footprint "RESC1608X55X30ML15T15")
      (fields (field (name "TOLERANCE") "5%") (field (name "Comment") "ERJ-3EKF4701V"))
      (libsource (lib "Altium Content Vault") (part "RES-2"))
    )
    (comp (ref "R32")
      (value "4.7k")
      (footprint "RESC1608X55X30ML15T15")
      (fields (field (name "TOLERANCE") "5%") (field (name "Comment") "ERJ-3EKF4701V"))
      (libsource (lib "Altium Content Vault") (part "RES-2"))
    )
    (comp (ref "R33")
      (value "120R")
      (footprint "RESC0805(2012)_L")
      (description "120R 0.125W 1% 0805 (2012 Metric)  SMD")
      (fields (field (name "TOLERANCE") "1 %") (field (name "POWER") "0.125 W"))
      (libsource (lib "Altium Content Vault") (part "RES"))
    )
    (comp (ref "SW1")
      (value "JS203011JCQN")
      (footprint "JS203011JCQN")
      (description "SWITCH SLIDE DP3T 300MA 6V")
      (fields (field (name "MANUFACTURER") "C&K") (field (name "DIGIKEY_PARTNUMBER") "CKN10725CT-ND"))
      (libsource (lib "Lapwing") (part "JS203011JCQN"))
    )
    (comp (ref "U1")
      (value "STM32L486VGT6")
      (footprint "STM-LQFP100_L")
      (fields (field (name "MANUFACTURER") "STMicroelectronics"))
      (libsource (lib "Altium Content Vault") (part "MC-ARM-STM32L4X6-LQFP100"))
    )
    (comp (ref "U2")
      (value "SN65HVD232D")
      (footprint "D0008A_M")
      (description "3.3 V CAN Transceiver, 17 mA, -40 to 85 degC, 8-pin SOIC (D), Green (RoHS & no Sb/Br)")
      (fields (field (name "MANUFACTURER") "Texas Instruments"))
      (libsource (lib "Altium Content Vault") (part "TI-SN65HVD232-SOIC_D-8"))
    )
    (comp (ref "U3")
      (value "W25M02GVZEIT")
      (footprint "WSON_VZEIT_WIN-M")
      (description "IC FLASH 2GBIT SPI 104MHZ 8WSON")
      (fields (field (name "SUPPLIER PART NUMBER 1") "W25M02GVZEITTR-ND"))
      (libsource (lib "Lapwing") (part "W25M02GVZEIT"))
    )
    (comp (ref "U4")
      (value "FT230XS-R")
      (footprint "U_FT230XS")
      (description "IC USB SERIAL BASIC UART 16SSOP")
      (fields
        (field (name "MP") "FT230XS")
        (field (name "MF") "FTDI, Future")
        (field (name "SUPPLIER PART NUMBER 1") "768-1135-1-ND")
      )
      (libsource (lib "Lapwing") (part "FT230XS-R"))
    )
    (comp (ref "U5")
      (value "LSM6DSLTR")
      (footprint "FP-LGA-14L-DM00249496-MFG")
      (description "IMU ACCEL/GYRO I2C/SPI 14LGA")
      (fields
        (field (name "MANUFACTURER") "STMicroelectronics")
        (field (name "OCTOPART") "https://octopart.com/lsm6dsltr-stmicroelectronics-66358193")
      )
      (libsource (lib "Altium Content Vault") (part "4e27e7d1829efda5344af1708d65448"))
    )
    (comp (ref "U6")
      (value "H3LIS331DLTR")
      (footprint "U_H3LIS331DLTR")
      (description "ACCEL 100-400G I2C/SPI 16TFLGA")
      (fields (field (name "MP") "H3LIS331DL") (field (name "MF") "STMicroelectronics"))
      (libsource (lib "Lapwing") (part "H3LIS331DLTR"))
    )
    (comp (ref "U7")
      (value "BMI088")
      (footprint "U_BMI088")
      (description "ACCELEROMETER 16LGA")
      (fields (field (name "MF") "Bosch Sensortec"))
      (libsource (lib "Lapwing") (part "BMI088"))
    )
    (comp (ref "U8")
      (value "LIS2MDLTR")
      (footprint "U_LIS2MDL")
      (description "SENSOR MR I2C/SPI 12LGA")
      (fields (field (name "DIGI-KEY_PART_NUMBER") "497-17588-1-ND") (field (name "MF") "STMicroelectronics"))
      (libsource (lib "Lapwing") (part "LIS2MDLTR"))
    )
    (comp (ref "U9")
      (value "MS560702BA03-50")
      (footprint "U_MS560702BA03-50")
      (description "BAROMETRIC PRESSURE SENSOR")
      (fields (field (name "MF") "TE Connectivity"))
      (libsource (lib "Lapwing") (part "MS560702BA03-50"))
    )
    (comp (ref "XTAL1")
      (value "32.768kHz")
      (footprint "X_NX3215SA")
      (description "CRYSTAL 32.768KHZ 6PF SMD")
      (fields
        (field (name "SUPPLIER PART NUMBER 1") "644-1386-1-ND")
        (field (name "Comment") "NX3215SA-32.768KHZ-EXS00A-MU00525")
      )
      (libsource (lib "Lapwing") (part "NX3215SA-32.768KHZ-EXS00A-MU00525"))
    )
    (comp (ref "XTAL2")
      (value "8MHz")
      (footprint "X_NX3225GD")
      (description "CRYSTAL 8.0000MHZ 8PF SMD")
      (fields
        (field (name "SUPPLIER PART NUMBER 1") "644-1178-1-ND")
        (field (name "Comment") "NX3225GD-8MHZ-STD-CRA-3")
      )
      (libsource (lib "Lapwing") (part "NX3225GD-8MHZ-STD-CRA-3"))
    )
  )
  (nets
    (net (code "1") (name "+3.3") (class "Default")
      (node (ref "C11") (pin "2") (pinfunction "2_2") (pintype "passive"))
      (node (ref "C14") (pin "2") (pinfunction "2_2") (pintype "passive"))
      (node (ref "C15") (pin "2") (pinfunction "2_2") (pintype "passive"))
      (node (ref "C16") (pin "2") (pinfunction "2_2") (pintype "passive"))
      (node (ref "C17") (pin "2") (pinfunction "2_2") (pintype "passive"))
      (node (ref "C19") (pin "2") (pinfunction "2_2") (pintype "passive"))
      (node (ref "C20") (pin "2") (pinfunction "2_2") (pintype "passive"))
      (node (ref "C21") (pin "2") (pinfunction "2_2") (pintype "passive"))
      (node (ref "C25") (pin "2") (pinfunction "2_2") (pintype "passive"))
      (node (ref "C28") (pin "2") (pinfunction "N/A_2") (pintype "passive"))
      (node (ref "C3") (pin "2") (pinfunction "2_2") (pintype "passive"))
      (node (ref "C30") (pin "2") (pinfunction "N/A_2") (pintype "passive"))
      (node (ref "C31") (pin "2") (pinfunction "N/A_2") (pintype "passive"))
      (node (ref "C32") (pin "1") (pinfunction "N/A_1") (pintype "passive"))
      (node (ref "C33") (pin "1") (pinfunction "N/A_1") (pintype "passive"))
      (node (ref "C34") (pin "1") (pinfunction "N/A_1") (pintype "passive"))
      (node (ref "C35") (pin "1") (pinfunction "N/A_1") (pintype "passive"))
      (node (ref "C36") (pin "1") (pinfunction "N/A_1") (pintype "passive"))
      (node (ref "C37") (pin "2") (pinfunction "N/A_2") (pintype "passive"))
      (node (ref "C38") (pin "1") (pinfunction "N/A_1") (pintype "passive"))
      (node (ref "C39") (pin "1") (pinfunction "N/A_1") (pintype "passive"))
      (node (ref "C40") (pin "1") (pinfunction "N/A_1") (pintype "passive"))
      (node (ref "C42") (pin "1") (pinfunction "1_1") (pintype "passive"))
      (node (ref "D1") (pin "1") (pinfunction "COMMON_ANODE_1") (pintype "passive"))
      (node (ref "D3") (pin "2") (pinfunction "A_2") (pintype "passive"))
      (node (ref "D9") (pin "1") (pinfunction "K_1") (pintype "passive"))
      (node (ref "DS1") (pin "1") (pinfunction "A_1") (pintype "passive"))
      (node (ref "F1") (pin "2") (pinfunction "2_2") (pintype "passive"))
      (node (ref "H1") (pin "1") (pinfunction "Vref_1") (pintype "passive"))
      (node (ref "J6") (pin "2") (pinfunction "2_2") (pintype "passive"))
      (node (ref "L3") (pin "1") (pinfunction "1_1") (pintype "passive"))
      (node (ref "P2") (pin "1") (pinfunction "1_1") (pintype "passive"))
      (node (ref "Q4") (pin "1") (pinfunction "G_1") (pintype "passive"))
      (node (ref "Q5") (pin "1") (pinfunction "G_1") (pintype "passive"))
      (node (ref "R18") (pin "2") (pinfunction "2_2") (pintype "passive"))
      (node (ref "R21") (pin "2") (pinfunction "2_2") (pintype "passive"))
      (node (ref "R22") (pin "2") (pinfunction "2_2") (pintype "passive"))
      (node (ref "R31") (pin "2") (pinfunction "2_2") (pintype "passive"))
      (node (ref "R32") (pin "2") (pinfunction "2_2") (pintype "passive"))
      (node (ref "R8") (pin "1") (pinfunction "1_1") (pintype "passive"))
      (node (ref "U1") (pin "100") (pinfunction "VDD_100") (pintype "power_in"))
      (node (ref "U1") (pin "11") (pinfunction "VDD_11") (pintype "power_in"))
      (node (ref "U1") (pin "28") (pinfunction "VDD_28") (pintype "power_in"))
      (node (ref "U1") (pin "50") (pinfunction "VDD_50") (pintype "power_in"))
      (node (ref "U1") (pin "6") (pinfunction "VBAT_6") (pintype "power_in"))
      (node (ref "U1") (pin "73") (pinfunction "VDDUSB_73") (pintype "power_in"))
      (node (ref "U1") (pin "75") (pinfunction "VDD_75") (pintype "power_in"))
      (node (ref "U2") (pin "3") (pinfunction "VCC_3") (pintype "power_in"))
      (node (ref "U3") (pin "8") (pinfunction "VCC_8") (pintype "power_in"))
      (node (ref "U5") (pin "5") (pinfunction "VDDIO_5") (pintype "power_in"))
      (node (ref "U5") (pin "8") (pinfunction "VDD_8") (pintype "power_in"))
      (node (ref "U6") (pin "1") (pinfunction "VDD_IO_1") (pintype "power_in"))
      (node (ref "U6") (pin "14") (pinfunction "VDD_14") (pintype "power_in"))
      (node (ref "U6") (pin "15") (pinfunction "VDD_15") (pintype "power_in"))
      (node (ref "U7") (pin "11") (pinfunction "VDDIO_11") (pintype "power_in"))
      (node (ref "U7") (pin "3") (pinfunction "VDD_3") (pintype "power_in"))
      (node (ref "U8") (pin "10") (pinfunction "VDD_IO_10") (pintype "power_in"))
      (node (ref "U8") (pin "9") (pinfunction "VDD_9") (pintype "power_in"))
      (node (ref "U9") (pin "1") (pinfunction "VDD_1") (pintype "power_in"))
    )
    (net (code "2") (name "+3.3A") (class "Default")
      (node (ref "C18") (pin "2") (pinfunction "2_2") (pintype "passive"))
      (node (ref "C23") (pin "2") (pinfunction "2_2") (pintype "passive"))
      (node (ref "C24") (pin "2") (pinfunction "2_2") (pintype "passive"))
      (node (ref "L3") (pin "2") (pinfunction "2_2") (pintype "passive"))
      (node (ref "U1") (pin "21") (pinfunction "VREF+_21") (pintype "power_in"))
      (node (ref "U1") (pin "22") (pinfunction "VDDA_22") (pintype "power_in"))
    )
    (net (code "3") (name "+5") (class "Default")
      (node (ref "D10") (pin "1") (pinfunction "K_1") (pintype "passive"))
      (node (ref "D2") (pin "2") (pinfunction "A_2") (pintype "passive"))
      (node (ref "F2") (pin "2") (pinfunction "2_2") (pintype "passive"))
      (node (ref "J7") (pin "2") (pinfunction "2_2") (pintype "passive"))
      (node (ref "R23") (pin "2") (pinfunction "2_2") (pintype "passive"))
      (node (ref "R24") (pin "2") (pinfunction "2_2") (pintype "passive"))
    )
    (net (code "4") (name "/ADC_BAT") (class "Default")
      (node (ref "C26") (pin "2") (pinfunction "N/A_2") (pintype "passive"))
      (node (ref "R25") (pin "2") (pintype "passive"))
      (node (ref "R26") (pin "2") (pintype "passive"))
      (node (ref "U1") (pin "17") (pinfunction "PC2_17") (pintype "bidirectional"))
    )
    (net (code "5") (name "/ADC_EMD") (class "Default")
      (node (ref "C27") (pin "2") (pinfunction "N/A_2") (pintype "passive"))
      (node (ref "R27") (pin "2") (pintype "passive"))
      (node (ref "R28") (pin "1") (pintype "passive"))
      (node (ref "U1") (pin "18") (pinfunction "PC3_18") (pintype "bidirectional"))
    )
    (net (code "6") (name "/ADC_EMM") (class "Default")
      (node (ref "C41") (pin "1") (pinfunction "N/A_1") (pintype "passive"))
      (node (ref "R29") (pin "1") (pintype "passive"))
      (node (ref "R30") (pin "1") (pintype "passive"))
      (node (ref "U1") (pin "23") (pinfunction "PA0_23") (pintype "bidirectional"))
    )
    (net (code "7") (name "/BAT+") (class "Default")
      (node (ref "J12") (pin "2") (pinfunction "2_2") (pintype "passive"))
      (node (ref "J12") (pin "4") (pinfunction "4_4") (pintype "passive"))
    )
    (net (code "8") (name "/BATH+") (class "Default")
      (node (ref "H2") (pin "1") (pinfunction "1_1") (pintype "passive"))
      (node (ref "H2") (pin "3") (pinfunction "3_3") (pintype "passive"))
    )
    (net (code "9") (name "/BUZZER") (class "Default")
      (node (ref "Q1") (pin "G") (pinfunction "G_G") (pintype "passive"))
      (node (ref "U1") (pin "24") (pinfunction "PA1_24") (pintype "bidirectional"))
    )
    (net (code "10") (name "/CAN_H") (class "Default")
      (node (ref "J11") (pin "1") (pinfunction "1_1") (pintype "passive"))
      (node (ref "R33") (pin "1") (pinfunction "1_1") (pintype "passive"))
      (node (ref "U2") (pin "7") (pinfunction "CANH_7") (pintype "bidirectional"))
    )
    (net (code "11") (name "/CAN_L") (class "Default")
      (node (ref "J13") (pin "2") (pinfunction "2_2") (pintype "passive"))
      (node (ref "R33") (pin "2") (pinfunction "2_2") (pintype "passive"))
      (node (ref "U2") (pin "6") (pinfunction "CANL_6") (pintype "bidirectional"))
    )
    (net (code "12") (name "/CAN_RX") (class "Default")
      (node (ref "U1") (pin "81") (pinfunction "PD0_81") (pintype "bidirectional"))
      (node (ref "U2") (pin "4") (pinfunction "R_4") (pintype "output"))
    )
    (net (code "13") (name "/CAN_TX") (class "Default")
      (node (ref "U1") (pin "82") (pinfunction "PD1_82") (pintype "bidirectional"))
      (node (ref "U2") (pin "1") (pinfunction "D_1") (pintype "input"))
    )
    (net (code "14") (name "/CS_ACCL") (class "Default")
      (node (ref "U1") (pin "59") (pinfunction "PD12_59") (pintype "bidirectional"))
      (node (ref "U7") (pin "14") (pinfunction "CSB1_14") (pintype "input"))
    )
    (net (code "15") (name "/CS_ALTIMU") (class "Default")
      (node (ref "U1") (pin "66") (pinfunction "PC9_66") (pintype "bidirectional"))
      (node (ref "U5") (pin "12") (pinfunction "CS_12") (pintype "input"))
    )
    (net (code "16") (name "/CS_BARO") (class "Default")
      (node (ref "U1") (pin "69") (pinfunction "PA10_69") (pintype "bidirectional"))
      (node (ref "U9") (pin "4") (pinfunction "~{CSB}_4") (pintype "input"))
      (node (ref "U9") (pin "5") (pinfunction "~{CSB}_5") (pintype "input"))
    )
    (net (code "17") (name "/CS_GYRO") (class "Default")
      (node (ref "U1") (pin "61") (pinfunction "PD14_61") (pintype "bidirectional"))
      (node (ref "U7") (pin "5") (pinfunction "CSB2_5") (pintype "input"))
    )
    (net (code "18") (name "/CS_HIACCL") (class "Default")
      (node (ref "U1") (pin "58") (pinfunction "PD11_58") (pintype "bidirectional"))
      (node (ref "U6") (pin "8") (pinfunction "CS_8") (pintype "input"))
    )
    (net (code "19") (name "/CS_MAG") (class "Default")
      (node (ref "U1") (pin "51") (pinfunction "PB12_51") (pintype "bidirectional"))
      (node (ref "U8") (pin "3") (pinfunction "CS_3") (pintype "input"))
    )
    (net (code "20") (name "/D1") (class "Default")
      (node (ref "J6") (pin "1") (pinfunction "1_1") (pintype "passive"))
      (node (ref "U1") (pin "15") (pinfunction "PC0_15") (pintype "bidirectional"))
    )
    (net (code "21") (name "/D2") (class "Default")
      (node (ref "J5") (pin "2") (pinfunction "2_2") (pintype "passive"))
      (node (ref "U1") (pin "16") (pinfunction "PC1_16") (pintype "bidirectional"))
    )
    (net (code "22") (name "/D3") (class "Default")
      (node (ref "J5") (pin "1") (pinfunction "1_1") (pintype "passive"))
      (node (ref "U1") (pin "25") (pinfunction "PA2_25") (pintype "bidirectional"))
    )
    (net (code "23") (name "/D4") (class "Default")
      (node (ref "J4") (pin "2") (pinfunction "2_2") (pintype "passive"))
      (node (ref "U1") (pin "26") (pinfunction "PA3_26") (pintype "bidirectional"))
    )
    (net (code "24") (name "/D5") (class "Default")
      (node (ref "J4") (pin "1") (pinfunction "1_1") (pintype "passive"))
      (node (ref "U1") (pin "30") (pinfunction "PA5_30") (pintype "bidirectional"))
    )
    (net (code "25") (name "/D6") (class "Default")
      (node (ref "J3") (pin "2") (pinfunction "2_2") (pintype "passive"))
      (node (ref "U1") (pin "31") (pinfunction "PA6_31") (pintype "bidirectional"))
    )
    (net (code "26") (name "/D7") (class "Default")
      (node (ref "J3") (pin "1") (pinfunction "1_1") (pintype "passive"))
      (node (ref "U1") (pin "32") (pinfunction "PA7_32") (pintype "bidirectional"))
    )
    (net (code "27") (name "/EMATCH_DROG") (class "Default")
      (node (ref "J12") (pin "8") (pinfunction "8_8") (pintype "passive"))
      (node (ref "Q2") (pin "D") (pinfunction "D_D") (pintype "passive"))
      (node (ref "R27") (pin "1") (pintype "passive"))
    )
    (net (code "28") (name "/EMATCH_MAIN") (class "Default")
      (node (ref "J12") (pin "7") (pinfunction "7_7") (pintype "passive"))
      (node (ref "Q3") (pin "D") (pinfunction "D_D") (pintype "passive"))
      (node (ref "R29") (pin "2") (pintype "passive"))
    )
    (net (code "29") (name "/FLASH_CLK") (class "Default")
      (node (ref "U1") (pin "47") (pinfunction "PB10_47") (pintype "bidirectional"))
      (node (ref "U3") (pin "6") (pinfunction "CLK_6") (pintype "passive"))
    )
    (net (code "30") (name "/FLASH_CS") (class "Default")
      (node (ref "U1") (pin "48") (pinfunction "PB11_48") (pintype "bidirectional"))
      (node (ref "U3") (pin "1") (pinfunction "CS_1") (pintype "passive"))
    )
    (net (code "31") (name "/FLASH_IO0") (class "Default")
      (node (ref "U1") (pin "43") (pinfunction "PE12_43") (pintype "bidirectional"))
      (node (ref "U3") (pin "5") (pinfunction "IO0_5") (pintype "passive"))
    )
    (net (code "32") (name "/FLASH_IO1") (class "Default")
      (node (ref "U1") (pin "44") (pinfunction "PE13_44") (pintype "bidirectional"))
      (node (ref "U3") (pin "2") (pinfunction "IO1_2") (pintype "passive"))
    )
    (net (code "33") (name "/FLASH_IO2") (class "Default")
      (node (ref "U1") (pin "45") (pinfunction "PE14_45") (pintype "bidirectional"))
      (node (ref "U3") (pin "3") (pinfunction "IO2_3") (pintype "passive"))
    )
    (net (code "34") (name "/FLASH_IO3") (class "Default")
      (node (ref "U1") (pin "46") (pinfunction "PE15_46") (pintype "bidirectional"))
      (node (ref "U3") (pin "7") (pinfunction "IO3_7") (pintype "passive"))
    )
    (net (code "35") (name "/H1") (class "Default")
      (node (ref "J8") (pin "2") (pinfunction "2_2") (pintype "passive"))
      (node (ref "Q4") (pin "3") (pinfunction "D_3") (pintype "passive"))
      (node (ref "R23") (pin "1") (pinfunction "1_1") (pintype "passive"))
    )
    (net (code "36") (name "/H2") (class "Default")
      (node (ref "J8") (pin "1") (pinfunction "1_1") (pintype "passive"))
      (node (ref "Q5") (pin "3") (pinfunction "D_3") (pintype "passive"))
      (node (ref "R24") (pin "1") (pinfunction "1_1") (pintype "passive"))
    )
    (net (code "37") (name "/HIO1_RAW") (class "Default")
      (node (ref "Q4") (pin "2") (pinfunction "S_2") (pintype "passive"))
      (node (ref "R21") (pin "1") (pinfunction "1_1") (pintype "passive"))
      (node (ref "U1") (pin "93") (pinfunction "PB7_93") (pintype "bidirectional"))
    )
    (net (code "38") (name "/HIO2_RAW") (class "Default")
      (node (ref "Q5") (pin "2") (pinfunction "S_2") (pintype "passive"))
      (node (ref "R22") (pin "1") (pinfunction "1_1") (pintype "passive"))
      (node (ref "U1") (pin "92") (pinfunction "PB6_92") (pintype "bidirectional"))
    )
    (net (code "39") (name "/INT_ACCL") (class "Default")
      (node (ref "U1") (pin "57") (pinfunction "PD10_57") (pintype "bidirectional"))
      (node (ref "U7") (pin "16") (pinfunction "INT1_16") (pintype "bidirectional"))
    )
    (net (code "40") (name "/INT_ALTIMU1") (class "Default")
      (node (ref "U1") (pin "65") (pinfunction "PC8_65") (pintype "bidirectional"))
      (node (ref "U5") (pin "4") (pinfunction "INT1_4") (pintype "input"))
    )
    (net (code "41") (name "/INT_ALTIMU2") (class "Default")
      (node (ref "U1") (pin "67") (pinfunction "PA8_67") (pintype "bidirectional"))
      (node (ref "U5") (pin "9") (pinfunction "INT2_9") (pintype "input"))
    )
    (net (code "42") (name "/INT_GYRO") (class "Default")
      (node (ref "U1") (pin "62") (pinfunction "PD15_62") (pintype "bidirectional"))
      (node (ref "U7") (pin "12") (pinfunction "INT3_12") (pintype "bidirectional"))
    )
    (net (code "43") (name "/INT_HIACCL") (class "Default")
      (node (ref "U1") (pin "60") (pinfunction "PD13_60") (pintype "bidirectional"))
      (node (ref "U6") (pin "11") (pinfunction "INT1_11") (pintype "output"))
    )
    (net (code "44") (name "/JTDI") (class "Default")
      (node (ref "H1") (pin "8") (pinfunction "TDI_8") (pintype "passive"))
      (node (ref "U1") (pin "77") (pinfunction "PA15(JTDI)_77") (pintype "bidirectional"))
    )
    (net (code "45") (name "/LED_BLUE") (class "Default")
      (node (ref "R14") (pin "2") (pinfunction "2_2") (pintype "passive"))
      (node (ref "U1") (pin "4") (pinfunction "PE5_4") (pintype "bidirectional"))
    )
    (net (code "46") (name "/LED_GREEN") (class "Default")
      (node (ref "R13") (pin "2") (pinfunction "2_2") (pintype "passive"))
      (node (ref "U1") (pin "3") (pinfunction "PE4_3") (pintype "bidirectional"))
    )
    (net (code "47") (name "/LED_RED") (class "Default")
      (node (ref "R12") (pin "2") (pinfunction "2_2") (pintype "passive"))
      (node (ref "U1") (pin "2") (pinfunction "PE3_2") (pintype "bidirectional"))
    )
    (net (code "48") (name "/LED_UART") (class "Default")
      (node (ref "R17") (pin "2") (pinfunction "2_2") (pintype "passive"))
      (node (ref "U4") (pin "14") (pinfunction "CBUS1_14") (pintype "bidirectional"))
    )
    (net (code "49") (name "/LED_USER") (class "Default")
      (node (ref "R11") (pin "2") (pinfunction "2_2") (pintype "passive"))
      (node (ref "U1") (pin "7") (pinfunction "PC13_7") (pintype "bidirectional"))
    )
    (net (code "50") (name "/MISO") (class "Default")
      (node (ref "J9") (pin "1") (pinfunction "1_1") (pintype "passive"))
      (node (ref "U1") (pin "53") (pinfunction "PB14_53") (pintype "bidirectional"))
      (node (ref "U5") (pin "1") (pinfunction "SDO/SA0_1") (pintype "output"))
      (node (ref "U6") (pin "7") (pinfunction "SDO/SA0_7") (pintype "bidirectional"))
      (node (ref "U7") (pin "10") (pinfunction "SDO2_10") (pintype "output"))
      (node (ref "U7") (pin "15") (pinfunction "SDO1_15") (pintype "output"))
      (node (ref "U8") (pin "7") (pinfunction "INT/DRDY/SDO_7") (pintype "bidirectional"))
      (node (ref "U9") (pin "6") (pinfunction "SDO_6") (pintype "output"))
    )
    (net (code "51") (name "/MOSI") (class "Default")
      (node (ref "J10") (pin "2") (pinfunction "2_2") (pintype "passive"))
      (node (ref "U1") (pin "54") (pinfunction "PB15_54") (pintype "bidirectional"))
      (node (ref "U5") (pin "14") (pinfunction "SDA_14") (pintype "output"))
      (node (ref "U6") (pin "6") (pinfunction "SDA/SDI/SDO_6") (pintype "bidirectional"))
      (node (ref "U7") (pin "9") (pinfunction "SDA/SDI_9") (pintype "bidirectional"))
      (node (ref "U8") (pin "4") (pinfunction "SDA/SDI/SDO_4") (pintype "bidirectional"))
      (node (ref "U9") (pin "7") (pinfunction "SDI/SDA_7") (pintype "bidirectional"))
    )
    (net (code "52") (name "/SCK") (class "Default")
      (node (ref "J9") (pin "2") (pinfunction "2_2") (pintype "passive"))
      (node (ref "U1") (pin "52") (pinfunction "PB13_52") (pintype "bidirectional"))
      (node (ref "U5") (pin "13") (pinfunction "SCL_13") (pintype "input"))
      (node (ref "U6") (pin "4") (pinfunction "SCL/SPC_4") (pintype "input"))
      (node (ref "U7") (pin "8") (pinfunction "SCL/SCK_8") (pintype "input"))
      (node (ref "U8") (pin "1") (pinfunction "SCL/SPC_1") (pintype "input"))
      (node (ref "U9") (pin "8") (pinfunction "SCLK_8") (pintype "input"))
    )
    (net (code "53") (name "/SCL") (class "Default")
      (node (ref "J10") (pin "1") (pinfunction "1_1") (pintype "passive"))
      (node (ref "R31") (pin "1") (pinfunction "1_1") (pintype "passive"))
      (node (ref "U1") (pin "95") (pinfunction "PB8_95") (pintype "bidirectional"))
    )
    (net (code "54") (name "/SDA") (class "Default")
      (node (ref "J11") (pin "2") (pinfunction "2_2") (pintype "passive"))
      (node (ref "R32") (pin "1") (pinfunction "1_1") (pintype "passive"))
      (node (ref "U1") (pin "96") (pinfunction "PB9_96") (pintype "bidirectional"))
    )
    (net (code "55") (name "/SEP_DROG") (class "Default")
      (node (ref "Q2") (pin "G") (pinfunction "G_G") (pintype "passive"))
      (node (ref "R19") (pin "2") (pinfunction "2_2") (pintype "passive"))
      (node (ref "U1") (pin "29") (pinfunction "PA4_29") (pintype "bidirectional"))
    )
    (net (code "56") (name "/SEP_MAIN") (class "Default")
      (node (ref "Q3") (pin "G") (pinfunction "G_G") (pintype "passive"))
      (node (ref "R20") (pin "2") (pinfunction "2_2") (pintype "passive"))
      (node (ref "U1") (pin "97") (pinfunction "PE0_97") (pintype "bidirectional"))
    )
    (net (code "57") (name "/SWCLK") (class "Default")
      (node (ref "H1") (pin "4") (pinfunction "CLK_4") (pintype "passive"))
      (node (ref "U1") (pin "76") (pinfunction "PA14(JTCK-SWCLK)_76") (pintype "bidirectional"))
    )
    (net (code "58") (name "/SWDIO") (class "Default")
      (node (ref "H1") (pin "2") (pinfunction "DIO_2") (pintype "passive"))
      (node (ref "U1") (pin "72") (pinfunction "PA13(JTMS-SWDIO)_72") (pintype "bidirectional"))
    )
    (net (code "59") (name "/SWO") (class "Default")
      (node (ref "H1") (pin "6") (pinfunction "SWO_6") (pintype "passive"))
      (node (ref "U1") (pin "89") (pinfunction "PB3(JTDO-TRACESWO)_89") (pintype "bidirectional"))
    )
    (net (code "60") (name "/SW_H") (class "Default")
      (node (ref "R8") (pin "2") (pinfunction "2_2") (pintype "passive"))
      (node (ref "SW1") (pin "4") (pinfunction "4_4") (pintype "passive"))
      (node (ref "SW1") (pin "8") (pinfunction "8_8") (pintype "passive"))
      (node (ref "U1") (pin "1") (pinfunction "PE2_1") (pintype "bidirectional"))
    )
    (net (code "61") (name "/UART_RX") (class "Default")
      (node (ref "U1") (pin "79") (pinfunction "PC11_79") (pintype "bidirectional"))
      (node (ref "U4") (pin "1") (pinfunction "TXD_1") (pintype "output"))
    )
    (net (code "62") (name "/UART_TX") (class "Default")
      (node (ref "U1") (pin "78") (pinfunction "PC10_78") (pintype "bidirectional"))
      (node (ref "U4") (pin "4") (pinfunction "RXD_4") (pintype "input"))
    )
    (net (code "63") (name "/USB1_N") (class "Default")
      (node (ref "J1") (pin "A7") (pinfunction "DN1_A7") (pintype "bidirectional"))
      (node (ref "J1") (pin "B7") (pinfunction "DN2_B7") (pintype "bidirectional"))
      (node (ref "U1") (pin "70") (pinfunction "PA11_70") (pintype "bidirectional"))
    )
    (net (code "64") (name "/USB1_P") (class "Default")
      (node (ref "J1") (pin "A6") (pinfunction "DP1_A6") (pintype "bidirectional"))
      (node (ref "J1") (pin "B6") (pinfunction "DP2_B6") (pintype "bidirectional"))
      (node (ref "U1") (pin "71") (pinfunction "PA12_71") (pintype "bidirectional"))
    )
    (net (code "65") (name "/USB1_VSENSE") (class "Default")
      (node (ref "R10") (pin "2") (pintype "passive"))
      (node (ref "R9") (pin "1") (pintype "passive"))
      (node (ref "U1") (pin "68") (pinfunction "PA9_68") (pintype "bidirectional"))
    )
    (net (code "66") (name "/USB2_N") (class "Default")
      (node (ref "C10") (pin "1") (pinfunction "1_1") (pintype "passive"))
      (node (ref "J2") (pin "A7") (pinfunction "DN1_A7") (pintype "bidirectional"))
      (node (ref "J2") (pin "B7") (pinfunction "DN2_B7") (pintype "bidirectional"))
      (node (ref "R7") (pin "1") (pinfunction "1_1") (pintype "passive"))
    )
    (net (code "67") (name "/USB2_P") (class "Default")
      (node (ref "C9") (pin "1") (pinfunction "1_1") (pintype "passive"))
      (node (ref "J2") (pin "A6") (pinfunction "DP1_A6") (pintype "bidirectional"))
      (node (ref "J2") (pin "B6") (pinfunction "DP2_B6") (pintype "bidirectional"))
      (node (ref "R6") (pin "1") (pinfunction "1_1") (pintype "passive"))
    )
    (net (code "68") (name "/nRST") (class "Default")
      (node (ref "C6") (pin "2") (pinfunction "2_2") (pintype "passive"))
      (node (ref "H1") (pin "10") (pinfunction "nRST_10") (pintype "passive"))
      (node (ref "SW1") (pin "1") (pinfunction "1_1") (pintype "passive"))
      (node (ref "SW1") (pin "5") (pinfunction "5_5") (pintype "passive"))
      (node (ref "U1") (pin "14") (pinfunction "NRST_14") (pintype "bidirectional"))
    )
    (net (code "69") (name "GND") (class "Default")
      (node (ref "C1") (pin "2") (pinfunction "N/A_2") (pintype "passive"))
      (node (ref "C10") (pin "2") (pinfunction "2_2") (pintype "passive"))
      (node (ref "C11") (pin "1") (pinfunction "1_1") (pintype "passive"))
      (node (ref "C12") (pin "2") (pinfunction "N/A_2") (pintype "passive"))
      (node (ref "C13") (pin "1") (pinfunction "N/A_1") (pintype "passive"))
      (node (ref "C14") (pin "1") (pinfunction "1_1") (pintype "passive"))
      (node (ref "C15") (pin "1") (pinfunction "1_1") (pintype "passive"))
      (node (ref "C16") (pin "1") (pinfunction "1_1") (pintype "passive"))
      (node (ref "C17") (pin "1") (pinfunction "1_1") (pintype "passive"))
      (node (ref "C18") (pin "1") (pinfunction "1_1") (pintype "passive"))
      (node (ref "C19") (pin "1") (pinfunction "1_1") (pintype "passive"))
      (node (ref "C2") (pin "1") (pinfunction "N/A_1") (pintype "passive"))
      (node (ref "C20") (pin "1") (pinfunction "1_1") (pintype "passive"))
      (node (ref "C21") (pin "1") (pinfunction "1_1") (pintype "passive"))
      (node (ref "C22") (pin "2") (pinfunction "2_2") (pintype "passive"))
      (node (ref "C23") (pin "1") (pinfunction "1_1") (pintype "passive"))
      (node (ref "C24") (pin "1") (pinfunction "1_1") (pintype "passive"))
      (node (ref "C25") (pin "1") (pinfunction "1_1") (pintype "passive"))
      (node (ref "C26") (pin "1") (pinfunction "N/A_1") (pintype "passive"))
      (node (ref "C27") (pin "1") (pinfunction "N/A_1") (pintype "passive"))
      (node (ref "C28") (pin "1") (pinfunction "N/A_1") (pintype "passive"))
      (node (ref "C29") (pin "2") (pinfunction "N/A_2") (pintype "passive"))
      (node (ref "C3") (pin "1") (pinfunction "1_1") (pintype "passive"))
      (node (ref "C30") (pin "1") (pinfunction "N/A_1") (pintype "passive"))
      (node (ref "C31") (pin "1") (pinfunction "N/A_1") (pintype "passive"))
      (node (ref "C32") (pin "2") (pinfunction "N/A_2") (pintype "passive"))
      (node (ref "C33") (pin "2") (pinfunction "N/A_2") (pintype "passive"))
      (node (ref "C34") (pin "2") (pinfunction "N/A_2") (pintype "passive"))
      (node (ref "C35") (pin "2") (pinfunction "N/A_2") (pintype "passive"))
      (node (ref "C36") (pin "2") (pinfunction "N/A_2") (pintype "passive"))
      (node (ref "C37") (pin "1") (pinfunction "N/A_1") (pintype "passive"))
      (node (ref "C38") (pin "2") (pinfunction "N/A_2") (pintype "passive"))
      (node (ref "C39") (pin "2") (pinfunction "N/A_2") (pintype "passive"))
      (node (ref "C4") (pin "1") (pinfunction "1_1") (pintype "passive"))
      (node (ref "C40") (pin "2") (pinfunction "N/A_2") (pintype "passive"))
      (node (ref "C41") (pin "2") (pinfunction "N/A_2") (pintype "passive"))
      (node (ref "C42") (pin "2") (pinfunction "2_2") (pintype "passive"))
      (node (ref "C43") (pin "2") (pinfunction "2_2") (pintype "passive"))
      (node (ref "C5") (pin "1") (pinfunction "1_1") (pintype "passive"))
      (node (ref "C6") (pin "1") (pinfunction "1_1") (pintype "passive"))
      (node (ref "C7") (pin "1") (pinfunction "1_1") (pintype "passive"))
      (node (ref "C8") (pin "1") (pinfunction "1_1") (pintype "passive"))
      (node (ref "C9") (pin "2") (pinfunction "2_2") (pintype "passive"))
      (node (ref "D10") (pin "2") (pinfunction "A_2") (pintype "passive"))
      (node (ref "D9") (pin "2") (pinfunction "A_2") (pintype "passive"))
      (node (ref "H1") (pin "3") (pinfunction "GND_3") (pintype "passive"))
      (node (ref "H1") (pin "5") (pinfunction "GND_5") (pintype "passive"))
      (node (ref "H2") (pin "2") (pinfunction "2_2") (pintype "passive"))
      (node (ref "J1") (pin "A1/B12") (pinfunction "GND_A1/B12") (pintype "power_in"))
      (node (ref "J1") (pin "B1/A12") (pinfunction "GND_B1/A12") (pintype "power_in"))
      (node (ref "J1") (pin "G1") (pinfunction "GND_G1") (pintype "power_in"))
      (node (ref "J1") (pin "G2") (pinfunction "GND_G2") (pintype "power_in"))
      (node (ref "J1") (pin "G3") (pinfunction "GND_G3") (pintype "power_in"))
      (node (ref "J1") (pin "G4") (pinfunction "GND_G4") (pintype "power_in"))
      (node (ref "J12") (pin "1") (pinfunction "1_1") (pintype "passive"))
      (node (ref "J12") (pin "3") (pinfunction "3_3") (pintype "passive"))
      (node (ref "J13") (pin "1") (pinfunction "1_1") (pintype "passive"))
      (node (ref "J2") (pin "A1/B12") (pinfunction "GND_A1/B12") (pintype "power_in"))
      (node (ref "J2") (pin "B1/A12") (pinfunction "GND_B1/A12") (pintype "power_in"))
      (node (ref "J2") (pin "G1") (pinfunction "GND_G1") (pintype "power_in"))
      (node (ref "J2") (pin "G2") (pinfunction "GND_G2") (pintype "power_in"))
      (node (ref "J2") (pin "G3") (pinfunction "GND_G3") (pintype "power_in"))
      (node (ref "J2") (pin "G4") (pinfunction "GND_G4") (pintype "power_in"))
      (node (ref "J7") (pin "1") (pinfunction "1_1") (pintype "passive"))
      (node (ref "P1") (pin "2") (pinfunction "2_2") (pintype "passive"))
      (node (ref "P2") (pin "2") (pinfunction "2_2") (pintype "passive"))
      (node (ref "Q1") (pin "S") (pinfunction "S_S") (pintype "passive"))
      (node (ref "Q2") (pin "S") (pinfunction "S_S") (pintype "passive"))
      (node (ref "Q3") (pin "S") (pinfunction "S_S") (pintype "passive"))
      (node (ref "R1") (pin "1") (pinfunction "1_1") (pintype "passive"))
      (node (ref "R10") (pin "1") (pintype "passive"))
      (node (ref "R15") (pin "2") (pinfunction "2_2") (pintype "passive"))
      (node (ref "R16") (pin "2") (pinfunction "2_2") (pintype "passive"))
      (node (ref "R19") (pin "1") (pinfunction "1_1") (pintype "passive"))
      (node (ref "R2") (pin "1") (pinfunction "1_1") (pintype "passive"))
      (node (ref "R20") (pin "1") (pinfunction "1_1") (pintype "passive"))
      (node (ref "R26") (pin "1") (pintype "passive"))
      (node (ref "R28") (pin "2") (pintype "passive"))
      (node (ref "R3") (pin "1") (pinfunction "1_1") (pintype "passive"))
      (node (ref "R30") (pin "2") (pintype "passive"))
      (node (ref "R4") (pin "1") (pinfunction "1_1") (pintype "passive"))
      (node (ref "R5") (pin "1") (pinfunction "1_1") (pintype "passive"))
      (node (ref "SW1") (pin "3") (pinfunction "3_3") (pintype "passive"))
      (node (ref "SW1") (pin "7") (pinfunction "7_7") (pintype "passive"))
      (node (ref "U1") (pin "10") (pinfunction "VSS_10") (pintype "power_in"))
      (node (ref "U1") (pin "19") (pinfunction "VSSA_19") (pintype "power_in"))
      (node (ref "U1") (pin "20") (pinfunction "VREF-_20") (pintype "power_in"))
      (node (ref "U1") (pin "27") (pinfunction "VSS_27") (pintype "power_in"))
      (node (ref "U1") (pin "49") (pinfunction "VSS_49") (pintype "power_in"))
      (node (ref "U1") (pin "74") (pinfunction "VSS_74") (pintype "power_in"))
      (node (ref "U1") (pin "99") (pinfunction "VSS_99") (pintype "power_in"))
      (node (ref "U2") (pin "2") (pinfunction "GND_2") (pintype "power_in"))
      (node (ref "U3") (pin "4") (pinfunction "GND_4") (pintype "power_in"))
      (node (ref "U4") (pin "13") (pinfunction "GND@1_13") (pintype "power_in"))
      (node (ref "U4") (pin "5") (pinfunction "GND_5") (pintype "power_in"))
      (node (ref "U5") (pin "2") (pinfunction "SDx_2") (pintype "passive"))
      (node (ref "U5") (pin "3") (pinfunction "SCx_3") (pintype "passive"))
      (node (ref "U5") (pin "6") (pinfunction "GND_6") (pintype "power_in"))
      (node (ref "U5") (pin "7") (pinfunction "GND_7") (pintype "power_in"))
      (node (ref "U6") (pin "10") (pinfunction "GND_10") (pintype "power_in"))
      (node (ref "U6") (pin "12") (pinfunction "GND_12") (pintype "power_in"))
      (node (ref "U6") (pin "13") (pinfunction "GND_13") (pintype "power_in"))
      (node (ref "U6") (pin "16") (pinfunction "GND_16") (pintype "power_in"))
      (node (ref "U6") (pin "5") (pinfunction "GND_5") (pintype "power_in"))
      (node (ref "U7") (pin "2") (pinfunction "NC_2") (pintype "passive"))
      (node (ref "U7") (pin "4") (pinfunction "GNDA_4") (pintype "power_in"))
      (node (ref "U7") (pin "6") (pinfunction "GNDIO_6") (pintype "power_in"))
      (node (ref "U7") (pin "7") (pinfunction "PS_7") (pintype "input"))
      (node (ref "U8") (pin "11") (pinfunction "NC2_11") (pintype "passive"))
      (node (ref "U8") (pin "12") (pinfunction "NC3_12") (pintype "passive"))
      (node (ref "U8") (pin "2") (pinfunction "NC1_2") (pintype "passive"))
      (node (ref "U8") (pin "6") (pinfunction "GND_6") (pintype "power_in"))
      (node (ref "U8") (pin "8") (pinfunction "GND_8") (pintype "power_in"))
      (node (ref "U9") (pin "2") (pinfunction "PS_2") (pintype "input"))
      (node (ref "U9") (pin "3") (pinfunction "GND_3") (pintype "power_in"))
    )
    (net (code "70") (name "Net-(C4-Pad2)") (class "Default")
      (node (ref "C4") (pin "2") (pinfunction "2_2") (pintype "passive"))
      (node (ref "J1") (pin "A4/B9") (pinfunction "VBUS_A4/B9") (pintype "power_in"))
      (node (ref "J1") (pin "B4/A9") (pinfunction "VBUS_B4/A9") (pintype "power_in"))
      (node (ref "L1") (pin "1") (pinfunction "1_1") (pintype "passive"))
    )
    (net (code "71") (name "Net-(C5-Pad2)") (class "Default")
      (node (ref "C5") (pin "2") (pinfunction "2_2") (pintype "passive"))
      (node (ref "J2") (pin "A4/B9") (pinfunction "VBUS_A4/B9") (pintype "power_in"))
      (node (ref "J2") (pin "B4/A9") (pinfunction "VBUS_B4/A9") (pintype "power_in"))
      (node (ref "L2") (pin "1") (pinfunction "1_1") (pintype "passive"))
    )
    (net (code "72") (name "Net-(D1-BLUE_C)") (class "Default")
      (node (ref "D1") (pin "2") (pinfunction "BLUE_C_2") (pintype "passive"))
      (node (ref "R14") (pin "1") (pinfunction "1_1") (pintype "passive"))
    )
    (net (code "73") (name "Net-(D1-GREEN_C)") (class "Default")
      (node (ref "D1") (pin "3") (pinfunction "GREEN_C_3") (pintype "passive"))
      (node (ref "R13") (pin "1") (pinfunction "1_1") (pintype "passive"))
    )
    (net (code "74") (name "Net-(D1-RED_C)") (class "Default")
      (node (ref "D1") (pin "4") (pinfunction "RED_C_4") (pintype "passive"))
      (node (ref "R12") (pin "1") (pinfunction "1_1") (pintype "passive"))
    )
    (net (code "75") (name "Net-(D2-C)") (class "Default")
      (node (ref "D2") (pin "1") (pinfunction "C_1") (pintype "passive"))
      (node (ref "R15") (pin "1") (pinfunction "1_1") (pintype "passive"))
    )
    (net (code "76") (name "Net-(D3-C)") (class "Default")
      (node (ref "D3") (pin "1") (pinfunction "C_1") (pintype "passive"))
      (node (ref "R16") (pin "1") (pinfunction "1_1") (pintype "passive"))
    )
    (net (code "77") (name "Net-(D4-C)") (class "Default")
      (node (ref "D4") (pin "1") (pinfunction "C_1") (pintype "passive"))
      (node (ref "R17") (pin "1") (pinfunction "1_1") (pintype "passive"))
    )
    (net (code "78") (name "Net-(DS1-K)") (class "Default")
      (node (ref "DS1") (pin "2") (pinfunction "K_2") (pintype "passive"))
      (node (ref "R11") (pin "1") (pinfunction "1_1") (pintype "passive"))
    )
    (net (code "79") (name "Net-(F1-Pad1)") (class "Default")
      (node (ref "F1") (pin "1") (pinfunction "1_1") (pintype "passive"))
      (node (ref "P1") (pin "3") (pinfunction "3_3") (pintype "passive"))
    )
    (net (code "80") (name "Net-(F2-Pad1)") (class "Default")
      (node (ref "F2") (pin "1") (pinfunction "1_1") (pintype "passive"))
      (node (ref "P2") (pin "3") (pinfunction "3_3") (pintype "passive"))
    )
    (net (code "81") (name "Net-(J1-CC1)") (class "Default")
      (node (ref "J1") (pin "A5") (pinfunction "CC1_A5") (pintype "bidirectional"))
      (node (ref "R1") (pin "2") (pinfunction "2_2") (pintype "passive"))
    )
    (net (code "82") (name "Net-(J1-CC2)") (class "Default")
      (node (ref "J1") (pin "B5") (pinfunction "CC2_B5") (pintype "bidirectional"))
      (node (ref "R3") (pin "2") (pinfunction "2_2") (pintype "passive"))
    )
    (net (code "83") (name "Net-(J2-CC1)") (class "Default")
      (node (ref "J2") (pin "A5") (pinfunction "CC1_A5") (pintype "bidirectional"))
      (node (ref "R2") (pin "2") (pinfunction "2_2") (pintype "passive"))
    )
    (net (code "84") (name "Net-(J2-CC2)") (class "Default")
      (node (ref "J2") (pin "B5") (pinfunction "CC2_B5") (pintype "bidirectional"))
      (node (ref "R4") (pin "2") (pinfunction "2_2") (pintype "passive"))
    )
    (net (code "85") (name "Net-(LS1-PadN)") (class "Default")
      (node (ref "LS1") (pin "N") (pinfunction "N_N") (pintype "passive"))
      (node (ref "Q1") (pin "D") (pinfunction "D_D") (pintype "passive"))
    )
    (net (code "86") (name "Net-(LS1-PadP)") (class "Default")
      (node (ref "LS1") (pin "P") (pinfunction "P_P") (pintype "passive"))
      (node (ref "R18") (pin "1") (pinfunction "1_1") (pintype "passive"))
    )
    (net (code "87") (name "Net-(U1A-BOOT0)") (class "Default")
      (node (ref "R5") (pin "2") (pinfunction "2_2") (pintype "passive"))
      (node (ref "U1") (pin "94") (pinfunction "BOOT0_94") (pintype "input"))
    )
    (net (code "88") (name "Net-(U1A-PC14-OSC32_IN(PC14))") (class "Default")
      (node (ref "C1") (pin "1") (pinfunction "N/A_1") (pintype "passive"))
      (node (ref "U1") (pin "8") (pinfunction "PC14-OSC32_IN(PC14)_8") (pintype "bidirectional"))
      (node (ref "XTAL1") (pin "2") (pintype "passive"))
    )
    (net (code "89") (name "Net-(U1A-PC15-OSC32_OUT(PC15))") (class "Default")
      (node (ref "C2") (pin "2") (pinfunction "N/A_2") (pintype "passive"))
      (node (ref "U1") (pin "9") (pinfunction "PC15-OSC32_OUT(PC15)_9") (pintype "bidirectional"))
      (node (ref "XTAL1") (pin "1") (pintype "passive"))
    )
    (net (code "90") (name "Net-(U1A-PH0-OSC_IN(PH0))") (class "Default")
      (node (ref "C12") (pin "1") (pinfunction "N/A_1") (pintype "passive"))
      (node (ref "U1") (pin "12") (pinfunction "PH0-OSC_IN(PH0)_12") (pintype "bidirectional"))
      (node (ref "XTAL2") (pin "2") (pintype "passive"))
    )
    (net (code "91") (name "Net-(U1A-PH1-OSC_OUT(PH1))") (class "Default")
      (node (ref "C13") (pin "2") (pinfunction "N/A_2") (pintype "passive"))
      (node (ref "U1") (pin "13") (pinfunction "PH1-OSC_OUT(PH1)_13") (pintype "bidirectional"))
      (node (ref "XTAL2") (pin "1") (pintype "passive"))
    )
    (net (code "92") (name "Net-(U4-USBDM)") (class "Default")
      (node (ref "R7") (pin "2") (pinfunction "2_2") (pintype "passive"))
      (node (ref "U4") (pin "9") (pinfunction "USBDM_9") (pintype "input"))
    )
    (net (code "93") (name "Net-(U4-USBDP)") (class "Default")
      (node (ref "R6") (pin "2") (pinfunction "2_2") (pintype "passive"))
      (node (ref "U4") (pin "8") (pinfunction "USBDP_8") (pintype "input"))
    )
    (net (code "94") (name "Net-(U8-C1)") (class "Default")
      (node (ref "C29") (pin "1") (pinfunction "N/A_1") (pintype "passive"))
      (node (ref "U8") (pin "5") (pinfunction "C1_5") (pintype "passive"))
    )
    (net (code "95") (name "UART_VIO") (class "Default")
      (node (ref "C22") (pin "1") (pinfunction "1_1") (pintype "passive"))
      (node (ref "D4") (pin "2") (pinfunction "A_2") (pintype "passive"))
      (node (ref "U4") (pin "10") (pinfunction "3V3OUT_10") (pintype "output"))
      (node (ref "U4") (pin "11") (pinfunction "~{RESET}_11") (pintype "input"))
      (node (ref "U4") (pin "3") (pinfunction "VCCIO_3") (pintype "power_in"))
    )
    (net (code "96") (name "USB1_VBUS") (class "Default")
      (node (ref "C7") (pin "2") (pinfunction "2_2") (pintype "passive"))
      (node (ref "D7") (pin "A") (pintype "passive"))
      (node (ref "L1") (pin "2") (pinfunction "2_2") (pintype "passive"))
      (node (ref "R9") (pin "2") (pintype "passive"))
    )
    (net (code "97") (name "USB2_VBUS") (class "Default")
      (node (ref "C8") (pin "2") (pinfunction "2_2") (pintype "passive"))
      (node (ref "D8") (pin "A") (pintype "passive"))
      (node (ref "L2") (pin "2") (pinfunction "2_2") (pintype "passive"))
      (node (ref "U4") (pin "12") (pinfunction "VCC_12") (pintype "power_in"))
    )
    (net (code "98") (name "VCC") (class "Default")
      (node (ref "C43") (pin "1") (pinfunction "1_1") (pintype "passive"))
      (node (ref "D5") (pin "A") (pintype "passive"))
      (node (ref "D6") (pin "A") (pintype "passive"))
      (node (ref "H2") (pin "4") (pinfunction "4_4") (pintype "passive"))
      (node (ref "J12") (pin "5") (pinfunction "5_5") (pintype "passive"))
      (node (ref "R25") (pin "1") (pintype "passive"))
    )
    (net (code "99") (name "VD") (class "Default")
      (node (ref "D6") (pin "K") (pintype "passive"))
      (node (ref "D7") (pin "K") (pintype "passive"))
      (node (ref "D8") (pin "K") (pintype "passive"))
      (node (ref "P1") (pin "1") (pinfunction "1_1") (pintype "passive"))
    )
    (net (code "100") (name "VQ") (class "Default")
      (node (ref "D5") (pin "K") (pintype "passive"))
      (node (ref "J12") (pin "6") (pinfunction "6_6") (pintype "passive"))
      (node (ref "J12") (pin "9") (pinfunction "9_9") (pintype "passive"))
    )
    (net (code "101") (name "unconnected-(H1-NC-Pad7)") (class "Default")
      (node (ref "H1") (pin "7") (pinfunction "NC_7") (pintype "passive+no_connect"))
    )
    (net (code "102") (name "unconnected-(H1-NC-Pad9)") (class "Default")
      (node (ref "H1") (pin "9") (pinfunction "NC_9") (pintype "passive+no_connect"))
    )
    (net (code "103") (name "unconnected-(J1-SBU1-PadA8)") (class "Default")
      (node (ref "J1") (pin "A8") (pinfunction "SBU1_A8") (pintype "bidirectional+no_connect"))
    )
    (net (code "104") (name "unconnected-(J1-SBU2-PadB8)") (class "Default")
      (node (ref "J1") (pin "B8") (pinfunction "SBU2_B8") (pintype "bidirectional+no_connect"))
    )
    (net (code "105") (name "unconnected-(J2-SBU1-PadA8)") (class "Default")
      (node (ref "J2") (pin "A8") (pinfunction "SBU1_A8") (pintype "bidirectional+no_connect"))
    )
    (net (code "106") (name "unconnected-(J2-SBU2-PadB8)") (class "Default")
      (node (ref "J2") (pin "B8") (pinfunction "SBU2_B8") (pintype "bidirectional+no_connect"))
    )
    (net (code "107") (name "unconnected-(P1-Pad4)") (class "Default")
      (node (ref "P1") (pin "4") (pinfunction "4_4") (pintype "passive+no_connect"))
    )
    (net (code "108") (name "unconnected-(P2-Pad4)") (class "Default")
      (node (ref "P2") (pin "4") (pinfunction "4_4") (pintype "passive+no_connect"))
    )
    (net (code "109") (name "unconnected-(SW1-Pad2)") (class "Default")
      (node (ref "SW1") (pin "2") (pinfunction "2_2") (pintype "passive+no_connect"))
    )
    (net (code "110") (name "unconnected-(SW1-Pad6)") (class "Default")
      (node (ref "SW1") (pin "6") (pinfunction "6_6") (pintype "passive+no_connect"))
    )
    (net (code "111") (name "unconnected-(U1A-PB0-Pad35)") (class "Default")
      (node (ref "U1") (pin "35") (pinfunction "PB0_35") (pintype "bidirectional+no_connect"))
    )
    (net (code "112") (name "unconnected-(U1A-PB1-Pad36)") (class "Default")
      (node (ref "U1") (pin "36") (pinfunction "PB1_36") (pintype "bidirectional+no_connect"))
    )
    (net (code "113") (name "unconnected-(U1A-PB2-Pad37)") (class "Default")
      (node (ref "U1") (pin "37") (pinfunction "PB2_37") (pintype "bidirectional+no_connect"))
    )
    (net (code "114") (name "unconnected-(U1A-PB4(NJTRST)-Pad90)") (class "Default")
      (node (ref "U1") (pin "90") (pinfunction "PB4(NJTRST)_90") (pintype "bidirectional+no_connect"))
    )
    (net (code "115") (name "unconnected-(U1A-PB5-Pad91)") (class "Default")
      (node (ref "U1") (pin "91") (pinfunction "PB5_91") (pintype "bidirectional+no_connect"))
    )
    (net (code "116") (name "unconnected-(U1A-PC4-Pad33)") (class "Default")
      (node (ref "U1") (pin "33") (pinfunction "PC4_33") (pintype "bidirectional+no_connect"))
    )
    (net (code "117") (name "unconnected-(U1A-PC5-Pad34)") (class "Default")
      (node (ref "U1") (pin "34") (pinfunction "PC5_34") (pintype "bidirectional+no_connect"))
    )
    (net (code "118") (name "unconnected-(U1A-PC6-Pad63)") (class "Default")
      (node (ref "U1") (pin "63") (pinfunction "PC6_63") (pintype "bidirectional+no_connect"))
    )
    (net (code "119") (name "unconnected-(U1A-PC7-Pad64)") (class "Default")
      (node (ref "U1") (pin "64") (pinfunction "PC7_64") (pintype "bidirectional+no_connect"))
    )
    (net (code "120") (name "unconnected-(U1A-PC12-Pad80)") (class "Default")
      (node (ref "U1") (pin "80") (pinfunction "PC12_80") (pintype "bidirectional+no_connect"))
    )
    (net (code "121") (name "unconnected-(U1A-PD2-Pad83)") (class "Default")
      (node (ref "U1") (pin "83") (pinfunction "PD2_83") (pintype "bidirectional+no_connect"))
    )
    (net (code "122") (name "unconnected-(U1A-PD3-Pad84)") (class "Default")
      (node (ref "U1") (pin "84") (pinfunction "PD3_84") (pintype "bidirectional+no_connect"))
    )
    (net (code "123") (name "unconnected-(U1A-PD4-Pad85)") (class "Default")
      (node (ref "U1") (pin "85") (pinfunction "PD4_85") (pintype "bidirectional"))
    )
    (net (code "124") (name "unconnected-(U1A-PD5-Pad86)") (class "Default")
      (node (ref "U1") (pin "86") (pinfunction "PD5_86") (pintype "bidirectional+no_connect"))
    )
    (net (code "125") (name "unconnected-(U1A-PD6-Pad87)") (class "Default")
      (node (ref "U1") (pin "87") (pinfunction "PD6_87") (pintype "bidirectional+no_connect"))
    )
    (net (code "126") (name "unconnected-(U1A-PD7-Pad88)") (class "Default")
      (node (ref "U1") (pin "88") (pinfunction "PD7_88") (pintype "bidirectional+no_connect"))
    )
    (net (code "127") (name "unconnected-(U1A-PD8-Pad55)") (class "Default")
      (node (ref "U1") (pin "55") (pinfunction "PD8_55") (pintype "bidirectional+no_connect"))
    )
    (net (code "128") (name "unconnected-(U1A-PD9-Pad56)") (class "Default")
      (node (ref "U1") (pin "56") (pinfunction "PD9_56") (pintype "bidirectional+no_connect"))
    )
    (net (code "129") (name "unconnected-(U1A-PE1-Pad98)") (class "Default")
      (node (ref "U1") (pin "98") (pinfunction "PE1_98") (pintype "bidirectional+no_connect"))
    )
    (net (code "130") (name "unconnected-(U1A-PE6-Pad5)") (class "Default")
      (node (ref "U1") (pin "5") (pinfunction "PE6_5") (pintype "bidirectional+no_connect"))
    )
    (net (code "131") (name "unconnected-(U1A-PE7-Pad38)") (class "Default")
      (node (ref "U1") (pin "38") (pinfunction "PE7_38") (pintype "bidirectional+no_connect"))
    )
    (net (code "132") (name "unconnected-(U1A-PE8-Pad39)") (class "Default")
      (node (ref "U1") (pin "39") (pinfunction "PE8_39") (pintype "bidirectional+no_connect"))
    )
    (net (code "133") (name "unconnected-(U1A-PE9-Pad40)") (class "Default")
      (node (ref "U1") (pin "40") (pinfunction "PE9_40") (pintype "bidirectional+no_connect"))
    )
    (net (code "134") (name "unconnected-(U1A-PE10-Pad41)") (class "Default")
      (node (ref "U1") (pin "41") (pinfunction "PE10_41") (pintype "bidirectional+no_connect"))
    )
    (net (code "135") (name "unconnected-(U1A-PE11-Pad42)") (class "Default")
      (node (ref "U1") (pin "42") (pinfunction "PE11_42") (pintype "bidirectional+no_connect"))
    )
    (net (code "136") (name "unconnected-(U2-NC-Pad5)") (class "Default")
      (node (ref "U2") (pin "5") (pinfunction "NC_5") (pintype "passive+no_connect"))
    )
    (net (code "137") (name "unconnected-(U2-NC-Pad8)") (class "Default")
      (node (ref "U2") (pin "8") (pinfunction "NC_8") (pintype "passive+no_connect"))
    )
    (net (code "138") (name "unconnected-(U4-CBUS0-Pad15)") (class "Default")
      (node (ref "U4") (pin "15") (pinfunction "CBUS0_15") (pintype "bidirectional+no_connect"))
    )
    (net (code "139") (name "unconnected-(U4-CBUS2-Pad7)") (class "Default")
      (node (ref "U4") (pin "7") (pinfunction "CBUS2_7") (pintype "bidirectional+no_connect"))
    )
    (net (code "140") (name "unconnected-(U4-CBUS3-Pad16)") (class "Default")
      (node (ref "U4") (pin "16") (pinfunction "CBUS3_16") (pintype "bidirectional+no_connect"))
    )
    (net (code "141") (name "unconnected-(U4-~{CTS}-Pad6)") (class "Default")
      (node (ref "U4") (pin "6") (pinfunction "~{CTS}_6") (pintype "input+no_connect"))
    )
    (net (code "142") (name "unconnected-(U4-~{RTS}-Pad2)") (class "Default")
      (node (ref "U4") (pin "2") (pinfunction "~{RTS}_2") (pintype "output+no_connect"))
    )
    (net (code "143") (name "unconnected-(U5-NC-Pad10)") (class "Default")
      (node (ref "U5") (pin "10") (pinfunction "NC_10") (pintype "passive+no_connect"))
    )
    (net (code "144") (name "unconnected-(U5-NC-Pad11)") (class "Default")
      (node (ref "U5") (pin "11") (pinfunction "NC_11") (pintype "passive+no_connect"))
    )
    (net (code "145") (name "unconnected-(U6-INT2-Pad9)") (class "Default")
      (node (ref "U6") (pin "9") (pinfunction "INT2_9") (pintype "output+no_connect"))
    )
    (net (code "146") (name "unconnected-(U7-INT2-Pad1)") (class "Default")
      (node (ref "U7") (pin "1") (pinfunction "INT2_1") (pintype "bidirectional+no_connect"))
    )
    (net (code "147") (name "unconnected-(U7-INT4-Pad13)") (class "Default")
      (node (ref "U7") (pin "13") (pinfunction "INT4_13") (pintype "bidirectional+no_connect"))
    )
  )
)
